# pi3_hat.net
KiCad netlist of a schematic drawn in EAGLE
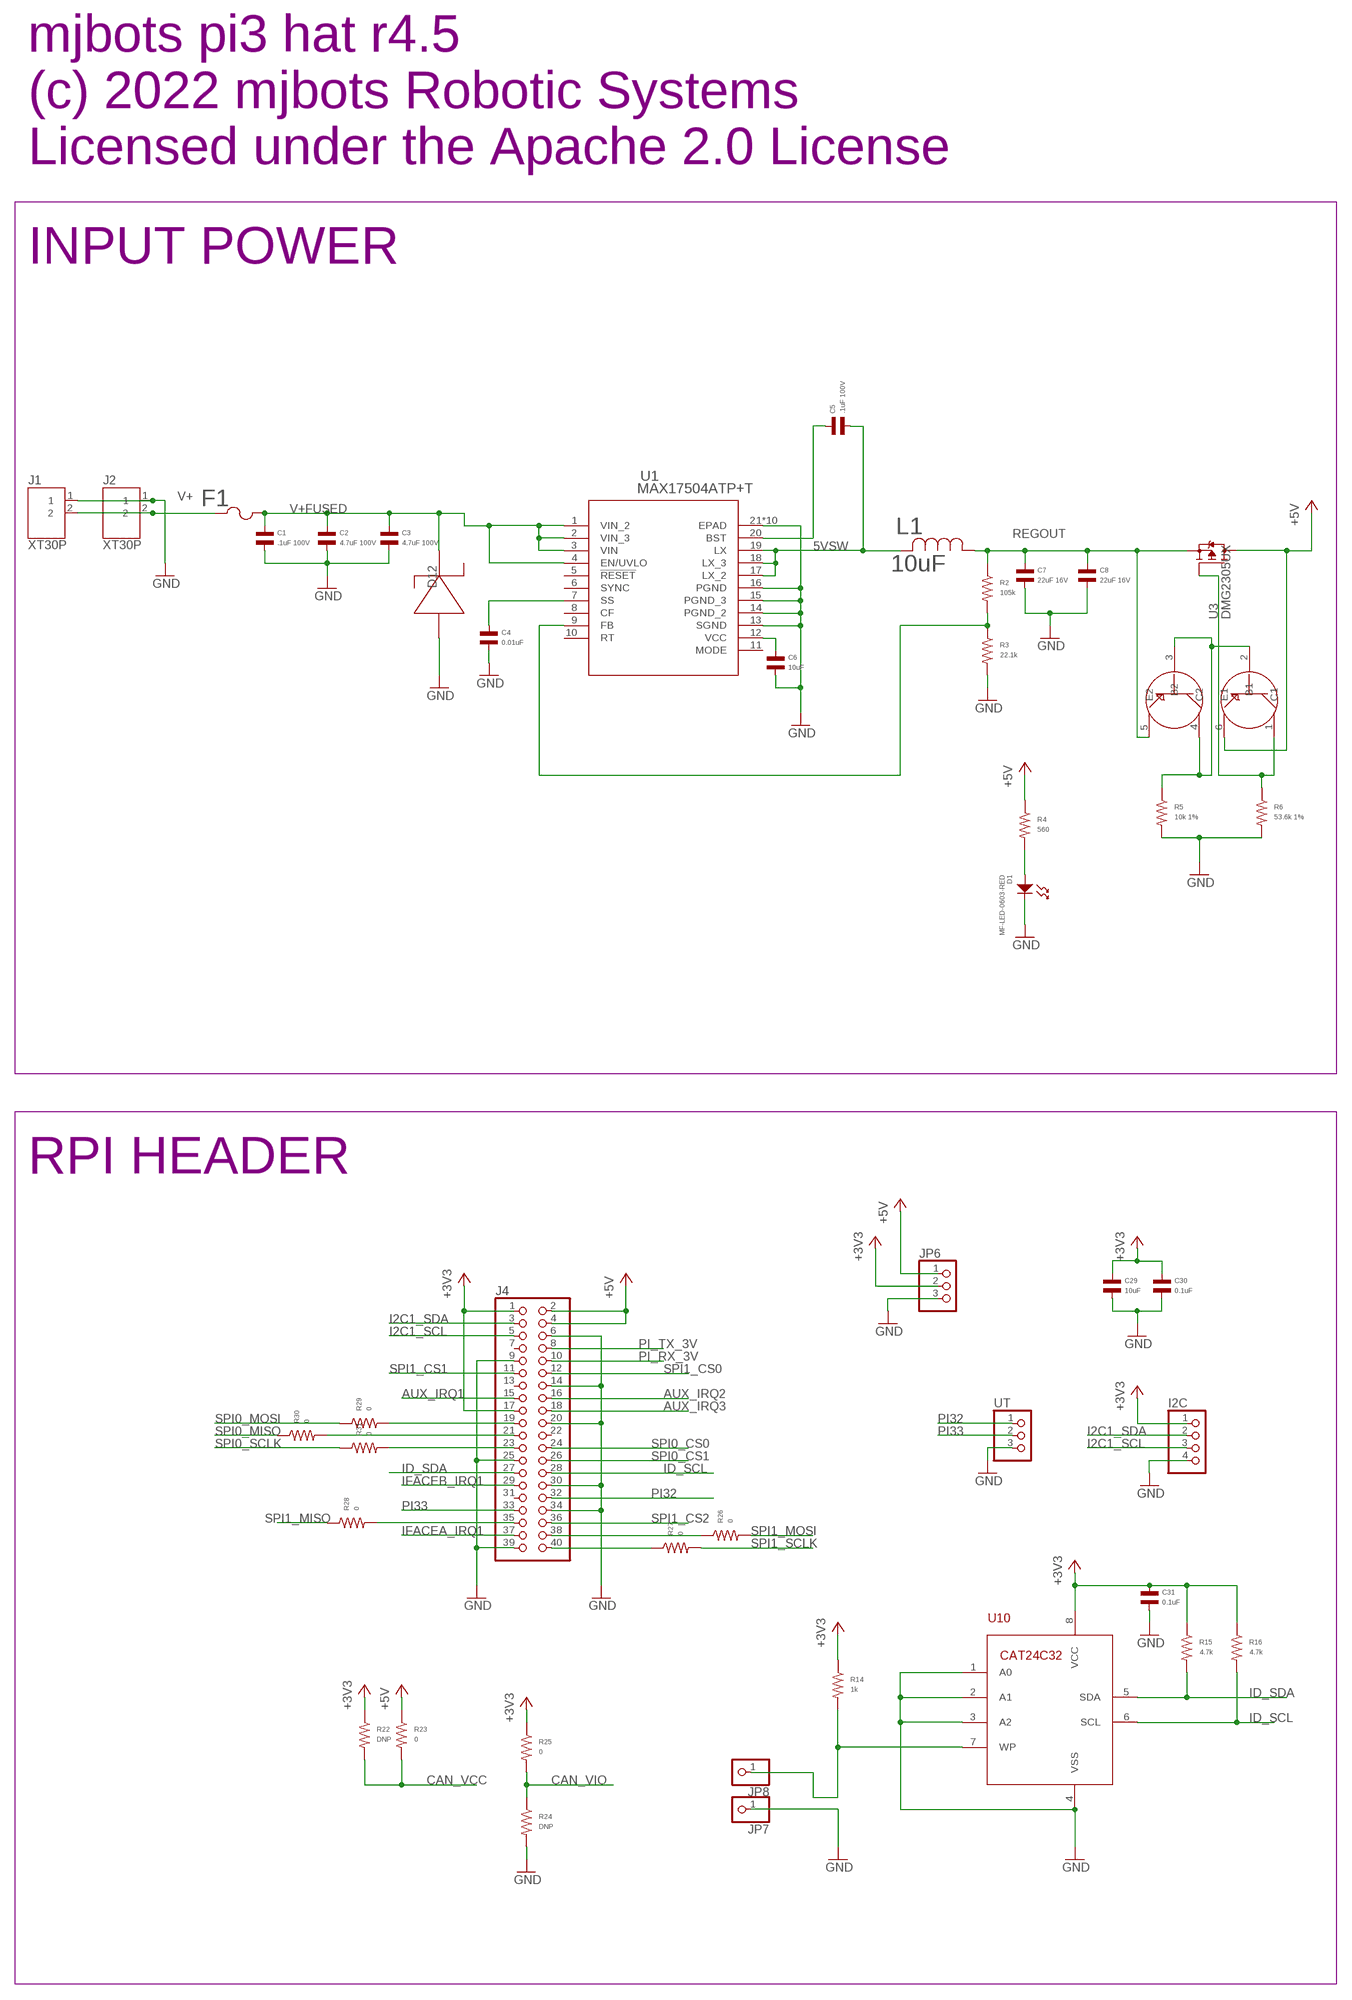
[diagram p0: schematic, sheet 1, part 1 of 3]
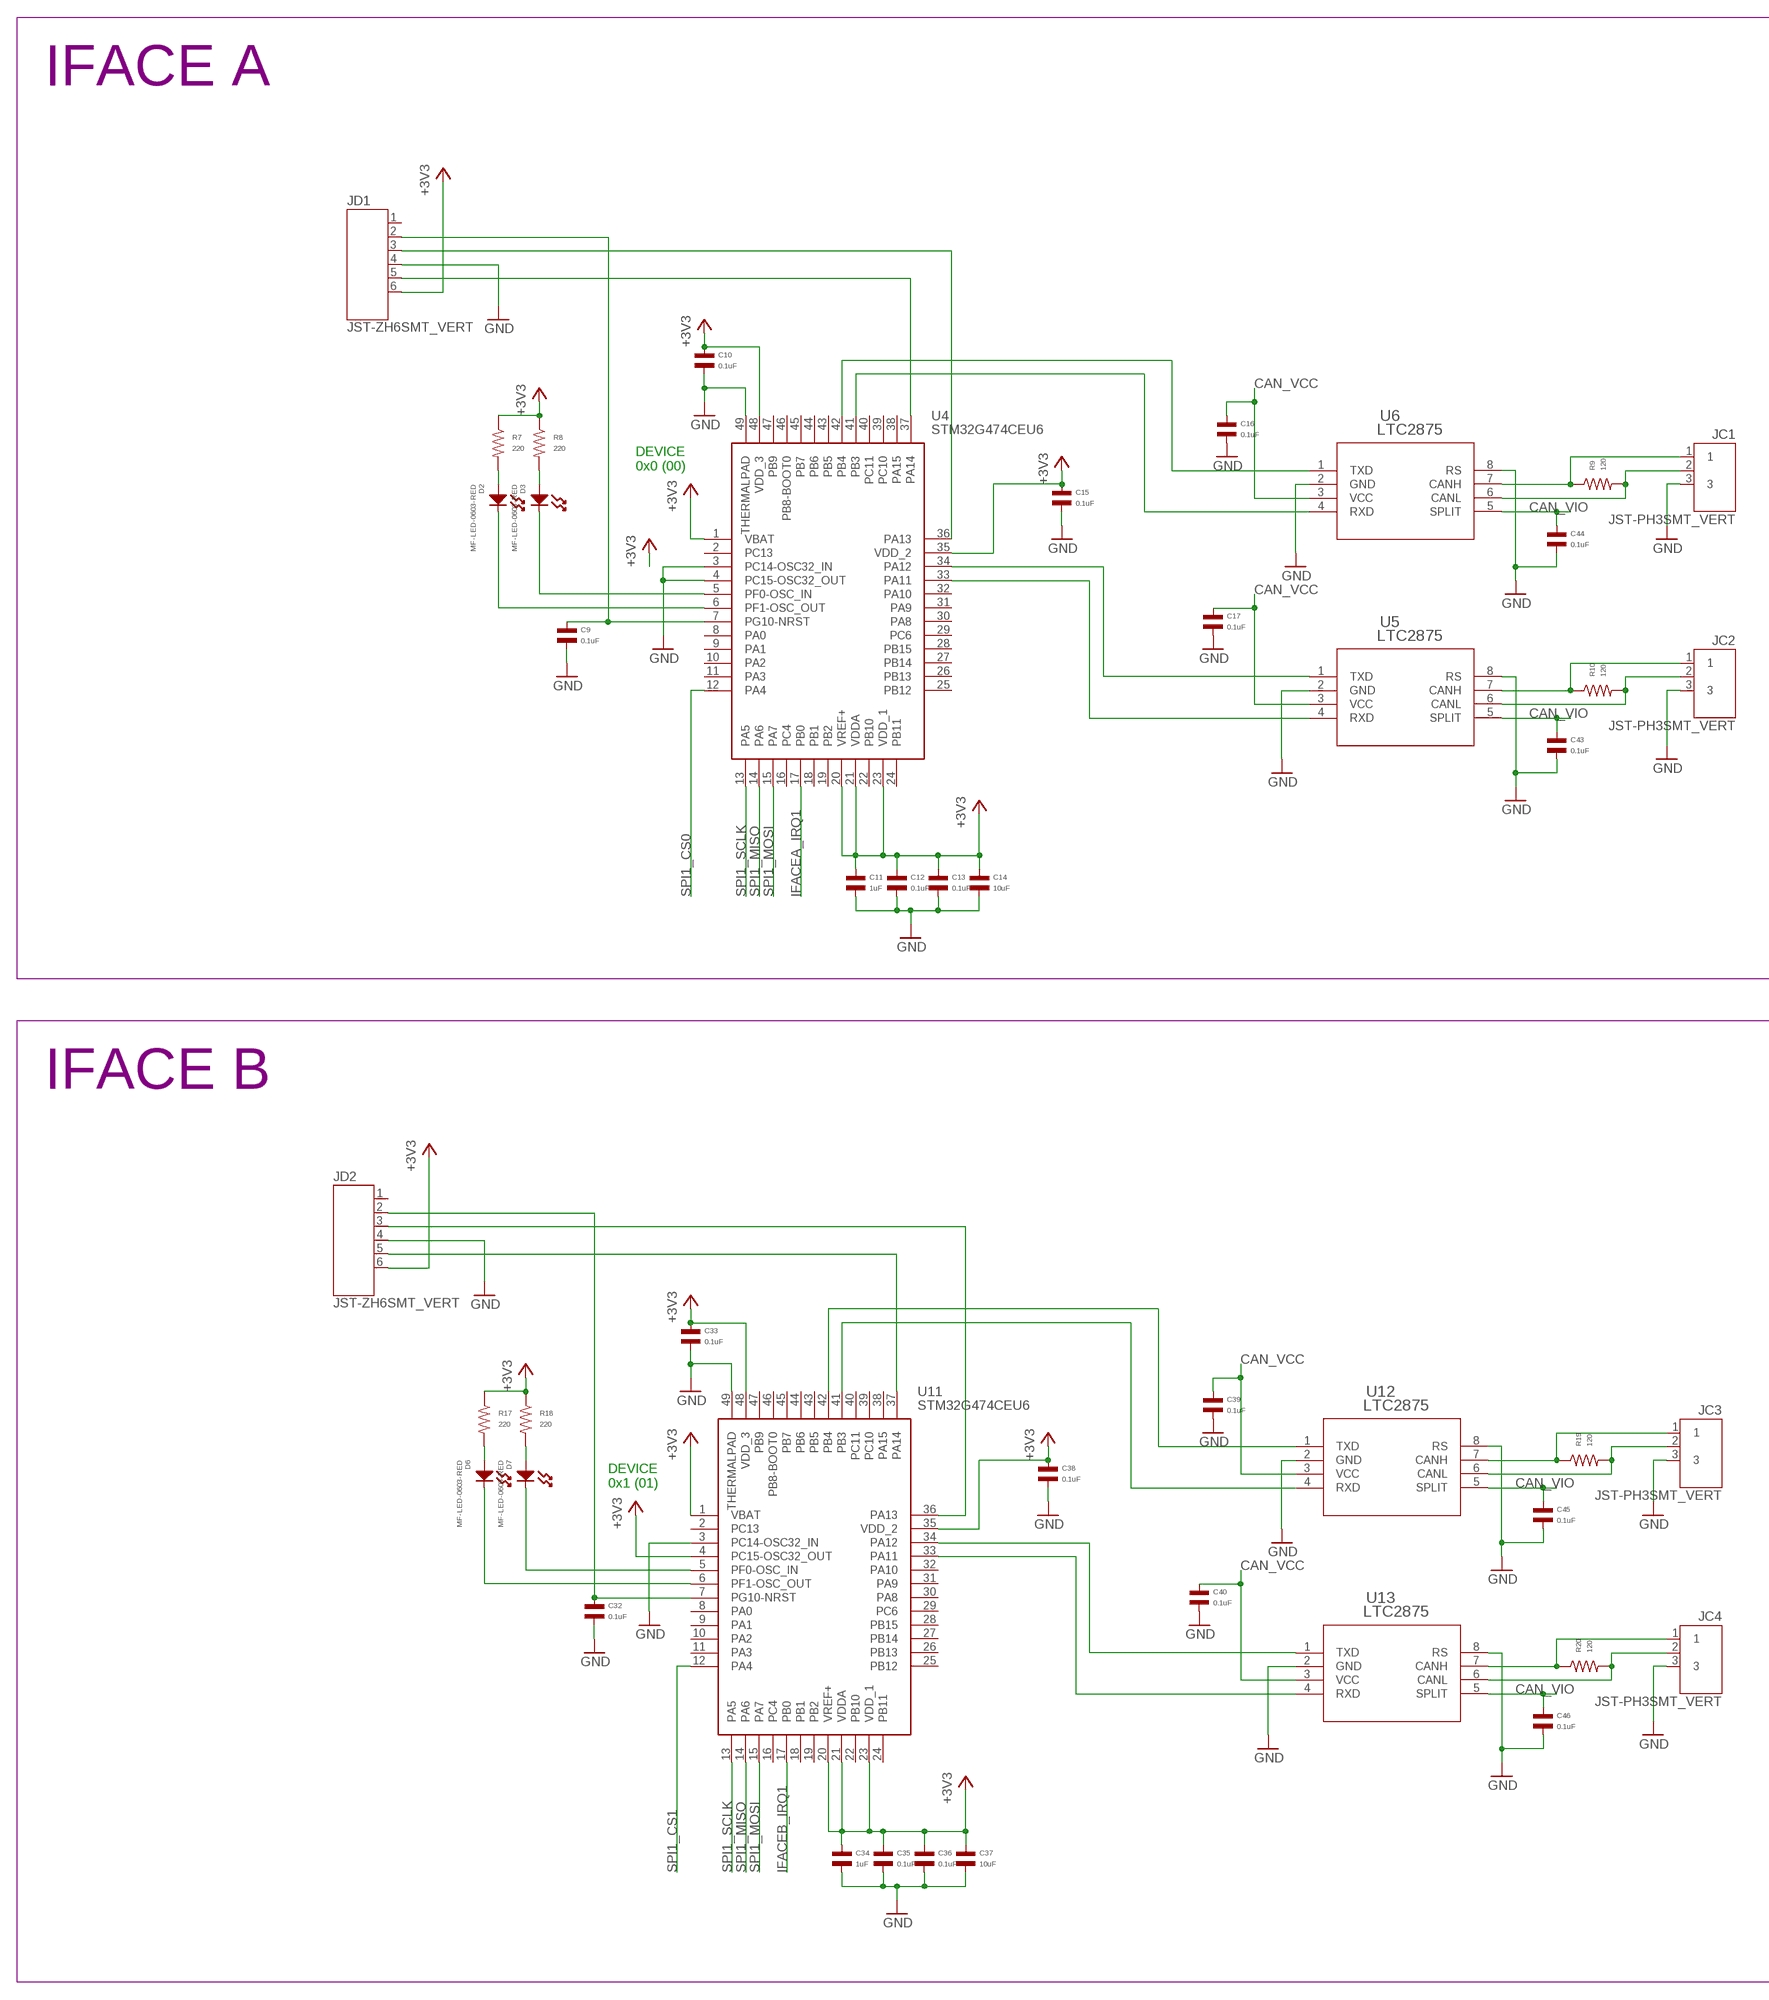
[diagram p1: schematic, sheet 1, part 2 of 3]
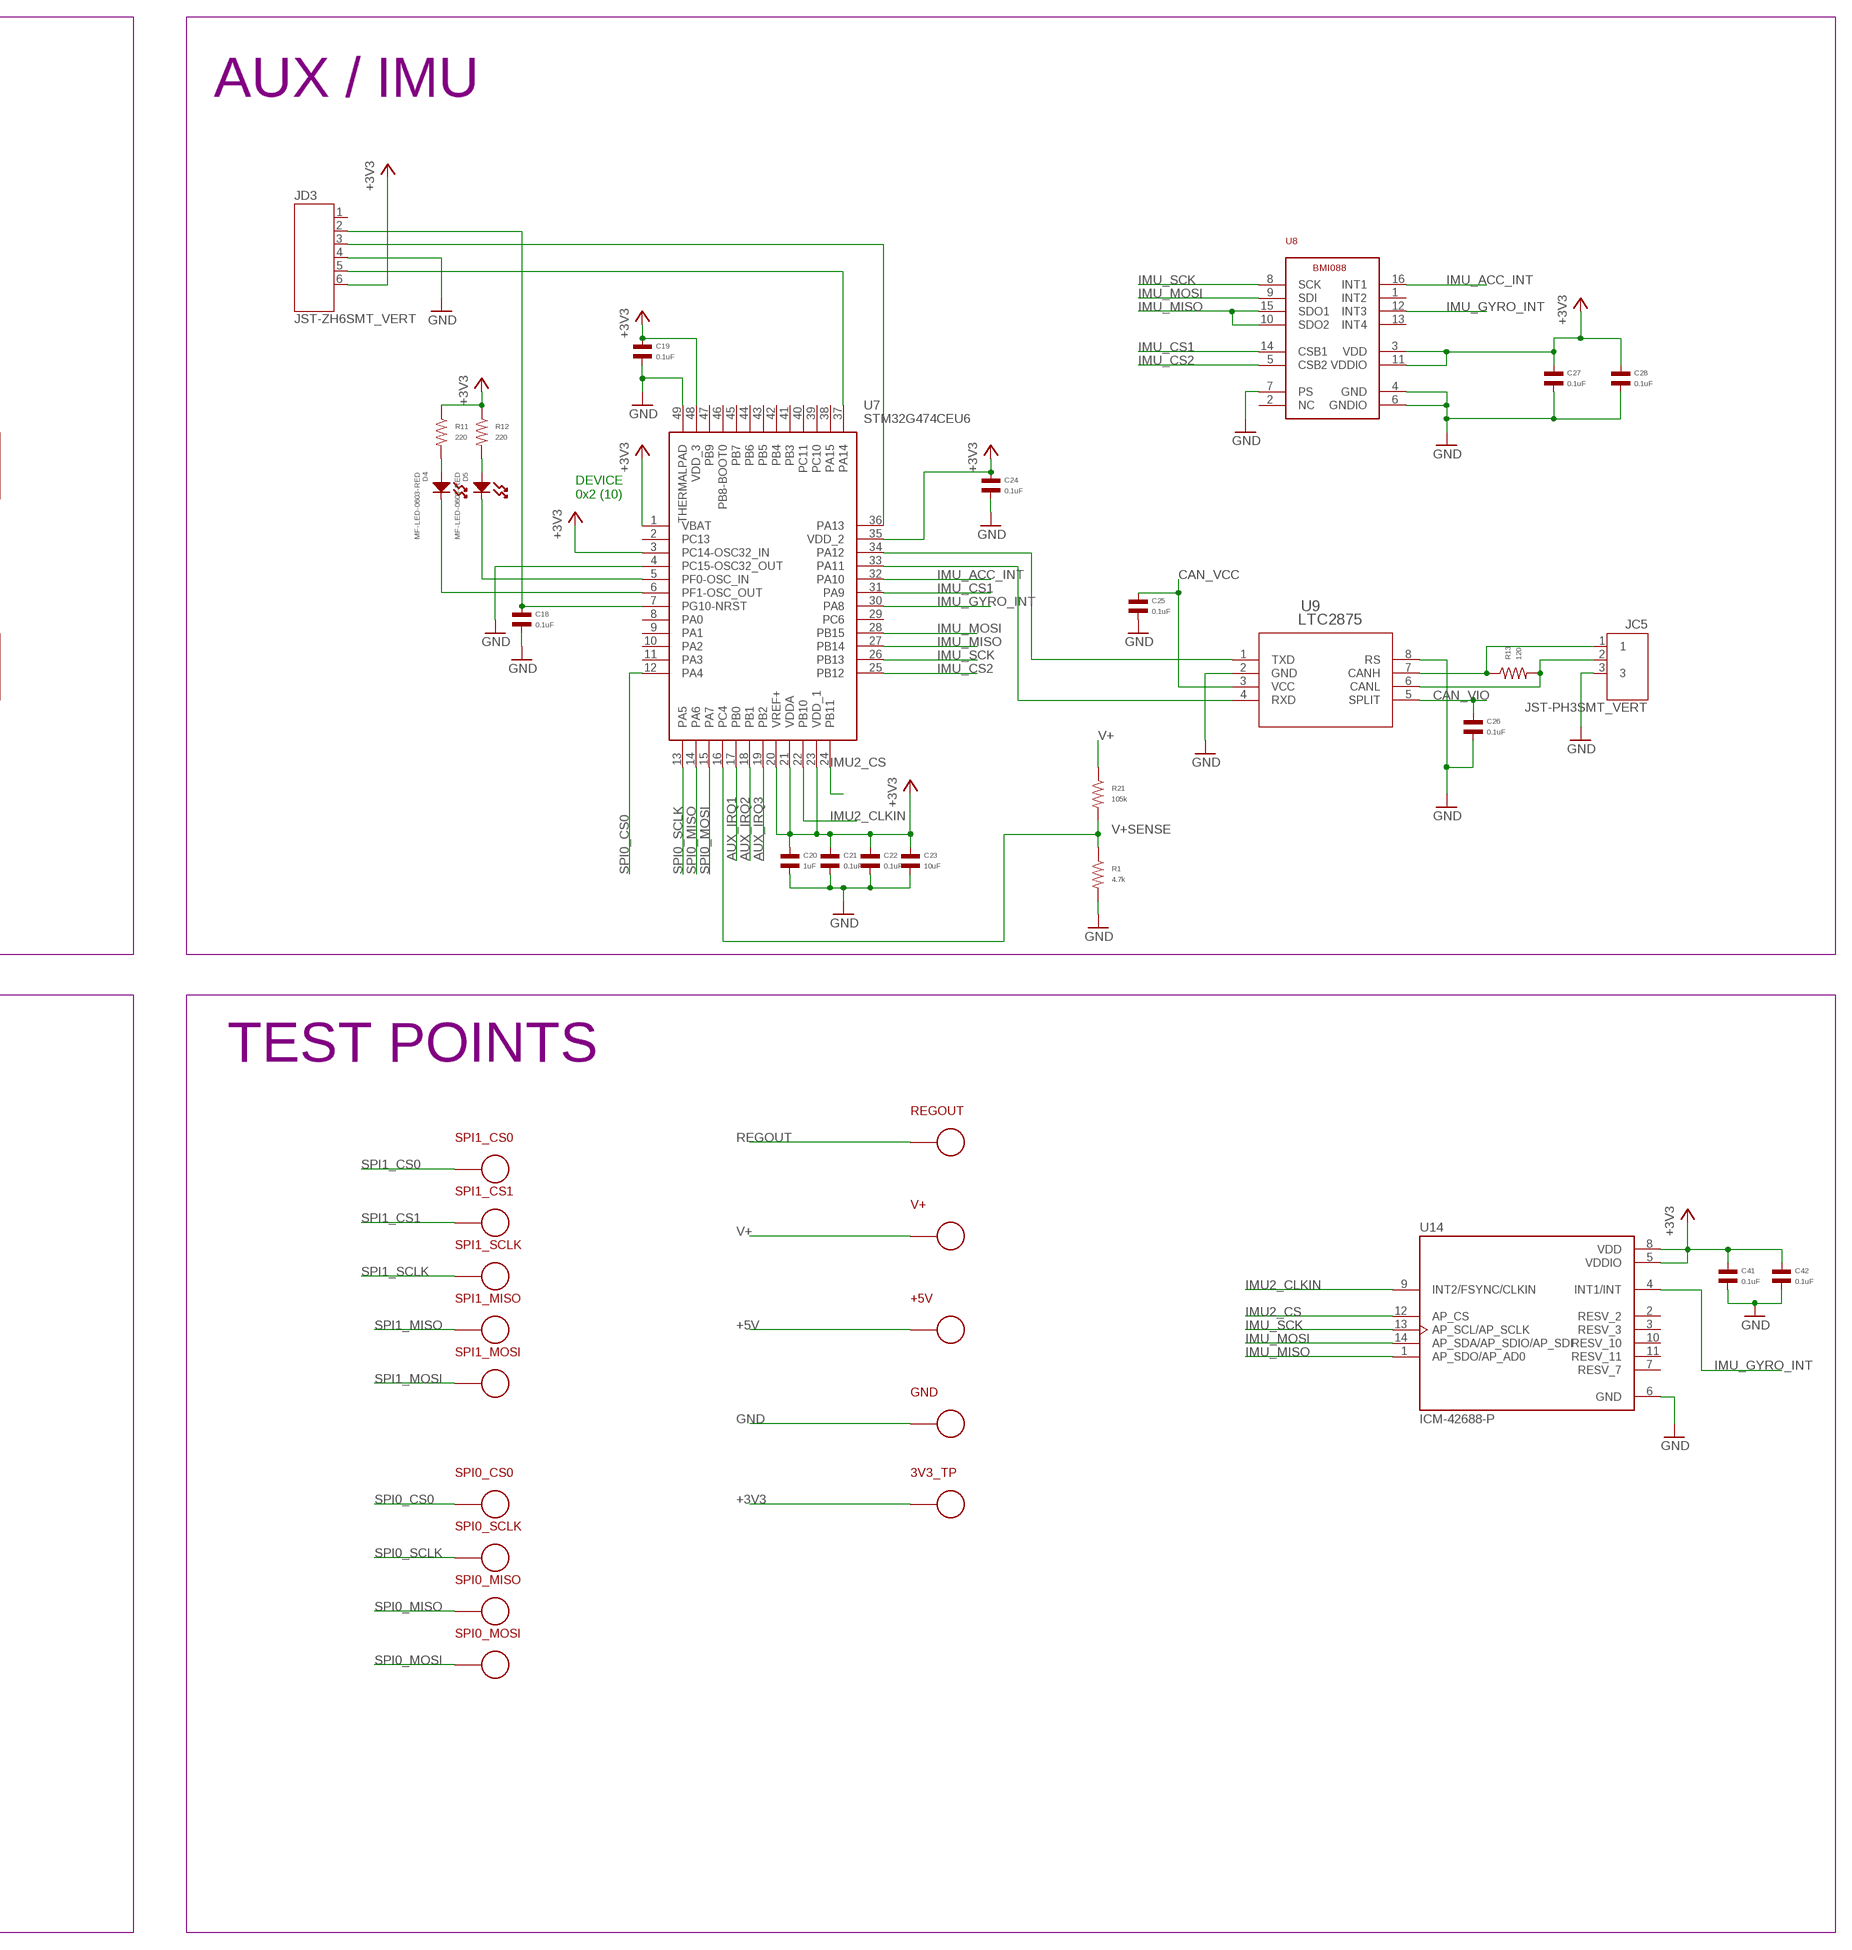
[diagram p2: schematic, sheet 1, part 3 of 3]

(export (version "E")
  (design (tool "Eeschema 10.0.6"))
  (components
    (comp (ref "+5V")
      (value "PAD24AWG_PAD")
      (footprint "eagle-import:24AWG_PAD")
      (libsource (lib "eagle-import") (part "PAD24AWG_PAD"))
    )
    (comp (ref "3V3_TP")
      (value "PAD24AWG_PAD")
      (footprint "eagle-import:24AWG_PAD")
      (libsource (lib "eagle-import") (part "PAD24AWG_PAD"))
    )
    (comp (ref "C1")
      (value ".1uF 100V")
      (footprint "eagle-import:C0805")
      (fields
        (field (name "HOUSEPART") "0")
        (field (name "MF") "KYOCERA")
        (field (name "MPN") "08051C104KAZ2A")
      )
      (libsource (lib "eagle-import") (part "CAPACITOR_NP_0805"))
    )
    (comp (ref "C2")
      (value "4.7uF 100V")
      (footprint "eagle-import:C1206")
      (fields (field (name "MF") "MURATA") (field (name "MPN") "GRJ31CC72A475KE01K"))
      (libsource (lib "eagle-import") (part "CAPACITOR_NP_1206"))
    )
    (comp (ref "C3")
      (value "4.7uF 100V")
      (footprint "eagle-import:C1206")
      (fields (field (name "MF") "MURATA") (field (name "MPN") "GRJ31CC72A475KE01K"))
      (libsource (lib "eagle-import") (part "CAPACITOR_NP_1206"))
    )
    (comp (ref "C4")
      (value "0.01uF")
      (footprint "eagle-import:C0603")
      (fields (field (name "MPN") "MF-CAP-0603-0.01uF"))
      (libsource (lib "eagle-import") (part "CAPACITOR_NP_0603"))
    )
    (comp (ref "C5")
      (value ".1uF 100V")
      (footprint "eagle-import:C0805")
      (fields
        (field (name "HOUSEPART") "0")
        (field (name "MF") "KYOCERA")
        (field (name "MPN") "08051C104KAZ2A")
      )
      (libsource (lib "eagle-import") (part "CAPACITOR_NP_0805"))
    )
    (comp (ref "C6")
      (value "10uF")
      (footprint "eagle-import:C1206")
      (fields (field (name "HOUSEPART") "YES") (field (name "MPN") "MF-CAP-1206-10uF"))
      (libsource (lib "eagle-import") (part "CAPACITOR_NP_1206"))
    )
    (comp (ref "C7")
      (value "22uF 16V")
      (footprint "eagle-import:C1210")
      (fields (field (name "MF") "SAMSUNG") (field (name "MPN") "CL32A226KOJNNNE"))
      (libsource (lib "eagle-import") (part "CAPACITOR_NP_1210"))
    )
    (comp (ref "C8")
      (value "22uF 16V")
      (footprint "eagle-import:C1210")
      (fields (field (name "MF") "SAMSUNG") (field (name "MPN") "CL32A226KOJNNNE"))
      (libsource (lib "eagle-import") (part "CAPACITOR_NP_1210"))
    )
    (comp (ref "C9")
      (value "0.1uF")
      (footprint "eagle-import:C0402")
      (fields (field (name "HOUSEPART") "YES") (field (name "MPN") "MF-CAP-0402-0.1uF"))
      (libsource (lib "eagle-import") (part "CAPACITOR_NP_0402"))
    )
    (comp (ref "C10")
      (value "0.1uF")
      (footprint "eagle-import:C0402")
      (fields (field (name "HOUSEPART") "YES") (field (name "MPN") "MF-CAP-0402-0.1uF"))
      (libsource (lib "eagle-import") (part "CAPACITOR_NP_0402"))
    )
    (comp (ref "C11")
      (value "1uF")
      (footprint "eagle-import:C0402")
      (fields (field (name "HOUSEPART") "YES") (field (name "MPN") "MF-CAP-0402-1uF"))
      (libsource (lib "eagle-import") (part "CAPACITOR_NP_0402"))
    )
    (comp (ref "C12")
      (value "0.1uF")
      (footprint "eagle-import:C0402")
      (fields (field (name "HOUSEPART") "YES") (field (name "MPN") "MF-CAP-0402-0.1uF"))
      (libsource (lib "eagle-import") (part "CAPACITOR_NP_0402"))
    )
    (comp (ref "C13")
      (value "0.1uF")
      (footprint "eagle-import:C0402")
      (fields (field (name "HOUSEPART") "YES") (field (name "MPN") "MF-CAP-0402-0.1uF"))
      (libsource (lib "eagle-import") (part "CAPACITOR_NP_0402"))
    )
    (comp (ref "C14")
      (value "10uF")
      (footprint "eagle-import:C1206")
      (fields (field (name "HOUSEPART") "YES") (field (name "MPN") "MF-CAP-1206-10uF"))
      (libsource (lib "eagle-import") (part "CAPACITOR_NP_1206"))
    )
    (comp (ref "C15")
      (value "0.1uF")
      (footprint "eagle-import:C0402")
      (fields (field (name "HOUSEPART") "YES") (field (name "MPN") "MF-CAP-0402-0.1uF"))
      (libsource (lib "eagle-import") (part "CAPACITOR_NP_0402"))
    )
    (comp (ref "C16")
      (value "0.1uF")
      (footprint "eagle-import:C0402")
      (fields (field (name "HOUSEPART") "YES") (field (name "MPN") "MF-CAP-0402-0.1uF"))
      (libsource (lib "eagle-import") (part "CAPACITOR_NP_0402"))
    )
    (comp (ref "C17")
      (value "0.1uF")
      (footprint "eagle-import:C0402")
      (fields (field (name "HOUSEPART") "YES") (field (name "MPN") "MF-CAP-0402-0.1uF"))
      (libsource (lib "eagle-import") (part "CAPACITOR_NP_0402"))
    )
    (comp (ref "C18")
      (value "0.1uF")
      (footprint "eagle-import:C0402")
      (fields (field (name "HOUSEPART") "YES") (field (name "MPN") "MF-CAP-0402-0.1uF"))
      (libsource (lib "eagle-import") (part "CAPACITOR_NP_0402"))
    )
    (comp (ref "C19")
      (value "0.1uF")
      (footprint "eagle-import:C0402")
      (fields (field (name "HOUSEPART") "YES") (field (name "MPN") "MF-CAP-0402-0.1uF"))
      (libsource (lib "eagle-import") (part "CAPACITOR_NP_0402"))
    )
    (comp (ref "C20")
      (value "1uF")
      (footprint "eagle-import:C0402")
      (fields (field (name "HOUSEPART") "YES") (field (name "MPN") "MF-CAP-0402-1uF"))
      (libsource (lib "eagle-import") (part "CAPACITOR_NP_0402"))
    )
    (comp (ref "C21")
      (value "0.1uF")
      (footprint "eagle-import:C0402")
      (fields (field (name "HOUSEPART") "YES") (field (name "MPN") "MF-CAP-0402-0.1uF"))
      (libsource (lib "eagle-import") (part "CAPACITOR_NP_0402"))
    )
    (comp (ref "C22")
      (value "0.1uF")
      (footprint "eagle-import:C0402")
      (fields (field (name "HOUSEPART") "YES") (field (name "MPN") "MF-CAP-0402-0.1uF"))
      (libsource (lib "eagle-import") (part "CAPACITOR_NP_0402"))
    )
    (comp (ref "C23")
      (value "10uF")
      (footprint "eagle-import:C1206")
      (fields (field (name "HOUSEPART") "YES") (field (name "MPN") "MF-CAP-1206-10uF"))
      (libsource (lib "eagle-import") (part "CAPACITOR_NP_1206"))
    )
    (comp (ref "C24")
      (value "0.1uF")
      (footprint "eagle-import:C0402")
      (fields (field (name "HOUSEPART") "YES") (field (name "MPN") "MF-CAP-0402-0.1uF"))
      (libsource (lib "eagle-import") (part "CAPACITOR_NP_0402"))
    )
    (comp (ref "C25")
      (value "0.1uF")
      (footprint "eagle-import:C0402")
      (fields (field (name "HOUSEPART") "YES") (field (name "MPN") "MF-CAP-0402-0.1uF"))
      (libsource (lib "eagle-import") (part "CAPACITOR_NP_0402"))
    )
    (comp (ref "C26")
      (value "0.1uF")
      (footprint "eagle-import:C0402")
      (fields (field (name "HOUSEPART") "YES") (field (name "MPN") "MF-CAP-0402-0.1uF"))
      (libsource (lib "eagle-import") (part "CAPACITOR_NP_0402"))
    )
    (comp (ref "C27")
      (value "0.1uF")
      (footprint "eagle-import:C0402")
      (fields (field (name "HOUSEPART") "YES") (field (name "MPN") "MF-CAP-0402-0.1uF"))
      (libsource (lib "eagle-import") (part "CAPACITOR_NP_0402"))
    )
    (comp (ref "C28")
      (value "0.1uF")
      (footprint "eagle-import:C0402")
      (fields (field (name "HOUSEPART") "YES") (field (name "MPN") "MF-CAP-0402-0.1uF"))
      (libsource (lib "eagle-import") (part "CAPACITOR_NP_0402"))
    )
    (comp (ref "C29")
      (value "10uF")
      (footprint "eagle-import:C1206")
      (fields (field (name "HOUSEPART") "YES") (field (name "MPN") "MF-CAP-1206-10uF"))
      (libsource (lib "eagle-import") (part "CAPACITOR_NP_1206"))
    )
    (comp (ref "C30")
      (value "0.1uF")
      (footprint "eagle-import:C0402")
      (fields (field (name "HOUSEPART") "YES") (field (name "MPN") "MF-CAP-0402-0.1uF"))
      (libsource (lib "eagle-import") (part "CAPACITOR_NP_0402"))
    )
    (comp (ref "C31")
      (value "0.1uF")
      (footprint "eagle-import:C0402")
      (fields (field (name "HOUSEPART") "YES") (field (name "MPN") "MF-CAP-0402-0.1uF"))
      (libsource (lib "eagle-import") (part "CAPACITOR_NP_0402"))
    )
    (comp (ref "C32")
      (value "0.1uF")
      (footprint "eagle-import:C0402")
      (fields (field (name "HOUSEPART") "YES") (field (name "MPN") "MF-CAP-0402-0.1uF"))
      (libsource (lib "eagle-import") (part "CAPACITOR_NP_0402"))
    )
    (comp (ref "C33")
      (value "0.1uF")
      (footprint "eagle-import:C0402")
      (fields (field (name "HOUSEPART") "YES") (field (name "MPN") "MF-CAP-0402-0.1uF"))
      (libsource (lib "eagle-import") (part "CAPACITOR_NP_0402"))
    )
    (comp (ref "C34")
      (value "1uF")
      (footprint "eagle-import:C0402")
      (fields (field (name "HOUSEPART") "YES") (field (name "MPN") "MF-CAP-0402-1uF"))
      (libsource (lib "eagle-import") (part "CAPACITOR_NP_0402"))
    )
    (comp (ref "C35")
      (value "0.1uF")
      (footprint "eagle-import:C0402")
      (fields (field (name "HOUSEPART") "YES") (field (name "MPN") "MF-CAP-0402-0.1uF"))
      (libsource (lib "eagle-import") (part "CAPACITOR_NP_0402"))
    )
    (comp (ref "C36")
      (value "0.1uF")
      (footprint "eagle-import:C0402")
      (fields (field (name "HOUSEPART") "YES") (field (name "MPN") "MF-CAP-0402-0.1uF"))
      (libsource (lib "eagle-import") (part "CAPACITOR_NP_0402"))
    )
    (comp (ref "C37")
      (value "10uF")
      (footprint "eagle-import:C1206")
      (fields (field (name "HOUSEPART") "YES") (field (name "MPN") "MF-CAP-1206-10uF"))
      (libsource (lib "eagle-import") (part "CAPACITOR_NP_1206"))
    )
    (comp (ref "C38")
      (value "0.1uF")
      (footprint "eagle-import:C0402")
      (fields (field (name "HOUSEPART") "YES") (field (name "MPN") "MF-CAP-0402-0.1uF"))
      (libsource (lib "eagle-import") (part "CAPACITOR_NP_0402"))
    )
    (comp (ref "C39")
      (value "0.1uF")
      (footprint "eagle-import:C0402")
      (fields (field (name "HOUSEPART") "YES") (field (name "MPN") "MF-CAP-0402-0.1uF"))
      (libsource (lib "eagle-import") (part "CAPACITOR_NP_0402"))
    )
    (comp (ref "C40")
      (value "0.1uF")
      (footprint "eagle-import:C0402")
      (fields (field (name "HOUSEPART") "YES") (field (name "MPN") "MF-CAP-0402-0.1uF"))
      (libsource (lib "eagle-import") (part "CAPACITOR_NP_0402"))
    )
    (comp (ref "C41")
      (value "0.1uF")
      (footprint "eagle-import:C0402")
      (fields (field (name "HOUSEPART") "YES") (field (name "MPN") "MF-CAP-0402-0.1uF"))
      (libsource (lib "eagle-import") (part "CAPACITOR_NP_0402"))
    )
    (comp (ref "C42")
      (value "0.1uF")
      (footprint "eagle-import:C0402")
      (fields (field (name "HOUSEPART") "YES") (field (name "MPN") "MF-CAP-0402-0.1uF"))
      (libsource (lib "eagle-import") (part "CAPACITOR_NP_0402"))
    )
    (comp (ref "C43")
      (value "0.1uF")
      (footprint "eagle-import:C0402")
      (fields (field (name "HOUSEPART") "YES") (field (name "MPN") "MF-CAP-0402-0.1uF"))
      (libsource (lib "eagle-import") (part "CAPACITOR_NP_0402"))
    )
    (comp (ref "C44")
      (value "0.1uF")
      (footprint "eagle-import:C0402")
      (fields (field (name "HOUSEPART") "YES") (field (name "MPN") "MF-CAP-0402-0.1uF"))
      (libsource (lib "eagle-import") (part "CAPACITOR_NP_0402"))
    )
    (comp (ref "C45")
      (value "0.1uF")
      (footprint "eagle-import:C0402")
      (fields (field (name "HOUSEPART") "YES") (field (name "MPN") "MF-CAP-0402-0.1uF"))
      (libsource (lib "eagle-import") (part "CAPACITOR_NP_0402"))
    )
    (comp (ref "C46")
      (value "0.1uF")
      (footprint "eagle-import:C0402")
      (fields (field (name "HOUSEPART") "YES") (field (name "MPN") "MF-CAP-0402-0.1uF"))
      (libsource (lib "eagle-import") (part "CAPACITOR_NP_0402"))
    )
    (comp (ref "D1")
      (value "MF-LED-0603-RED")
      (footprint "eagle-import:LED0603")
      (fields (field (name "HOUSEPART") "YES"))
      (libsource (lib "eagle-import") (part "LED_SINGLE-0603-RED"))
    )
    (comp (ref "D2")
      (value "MF-LED-0603-RED")
      (footprint "eagle-import:LED0603")
      (fields (field (name "HOUSEPART") "YES"))
      (libsource (lib "eagle-import") (part "LED_SINGLE-0603-RED"))
    )
    (comp (ref "D3")
      (value "MF-LED-0603-RED")
      (footprint "eagle-import:LED0603")
      (fields (field (name "HOUSEPART") "YES") (field (name "MPN") "MF-LED-0603-GREEN"))
      (libsource (lib "eagle-import") (part "LED_SINGLE-0603-RED"))
    )
    (comp (ref "D4")
      (value "MF-LED-0603-RED")
      (footprint "eagle-import:LED0603")
      (fields (field (name "HOUSEPART") "YES"))
      (libsource (lib "eagle-import") (part "LED_SINGLE-0603-RED"))
    )
    (comp (ref "D5")
      (value "MF-LED-0603-RED")
      (footprint "eagle-import:LED0603")
      (fields (field (name "HOUSEPART") "YES") (field (name "MPN") "MF-LED-0603-GREEN"))
      (libsource (lib "eagle-import") (part "LED_SINGLE-0603-RED"))
    )
    (comp (ref "D6")
      (value "MF-LED-0603-RED")
      (footprint "eagle-import:LED0603")
      (fields (field (name "HOUSEPART") "YES"))
      (libsource (lib "eagle-import") (part "LED_SINGLE-0603-RED"))
    )
    (comp (ref "D7")
      (value "MF-LED-0603-RED")
      (footprint "eagle-import:LED0603")
      (fields (field (name "HOUSEPART") "YES") (field (name "MPN") "MF-LED-0603-GREEN"))
      (libsource (lib "eagle-import") (part "LED_SINGLE-0603-RED"))
    )
    (comp (ref "D12")
      (value "SMF")
      (footprint "eagle-import:SMF")
      (fields (field (name "MF") "LITTLEFUSE") (field (name "MPN") "SMF51A"))
      (libsource (lib "eagle-import") (part "SMF"))
    )
    (comp (ref "F1")
      (value "MFU0603FF04000P100")
      (footprint "eagle-import:FUS_VISHAY_MFU0603")
      (fields
        (field (name "MF") "BEL FUSE")
        (field (name "MPN") "0686F4000-01")
        (field (name "VENDOR") "BEL FUSE")
      )
      (libsource (lib "eagle-import") (part "MFU0603FF04000P100"))
    )
    (comp (ref "GND")
      (value "PAD24AWG_PAD")
      (footprint "eagle-import:24AWG_PAD")
      (libsource (lib "eagle-import") (part "PAD24AWG_PAD"))
    )
    (comp (ref "I2C")
      (value "PINHD-1X4")
      (footprint "eagle-import:1X04")
      (fields (field (name "MF") "MacroFab") (field (name "MPN") "MF-CON-2.54mm-01x04"))
      (libsource (lib "eagle-import") (part "PINHD-1X4"))
    )
    (comp (ref "J1")
      (value "XT30P")
      (footprint "eagle-import:XT30P")
      (fields (field (name "MF") "AMASS") (field (name "MPN") "XT30UPB-M"))
      (libsource (lib "eagle-import") (part "XT30P"))
    )
    (comp (ref "J2")
      (value "XT30P")
      (footprint "eagle-import:XT30P")
      (fields (field (name "MF") "AMASS") (field (name "MPN") "XT30UPB-M"))
      (libsource (lib "eagle-import") (part "XT30P"))
    )
    (comp (ref "J4")
      (value "PI3_HEADER2X20-FLIP")
      (footprint "eagle-import:2X20FLIP")
      (fields (field (name "MF") "SULLINS") (field (name "MPN") "PPPC202LFBN-RC"))
      (libsource (lib "eagle-import") (part "PI3_HEADER2X20-FLIP"))
    )
    (comp (ref "JC1")
      (value "JST-PH3SMT_VERT")
      (footprint "eagle-import:JST_B3B_PH-SM4-TB(LF)(SN)")
      (fields (field (name "MF") "JST") (field (name "MPN") "B3B-PH-SM4-TB(LF)(SN)"))
      (libsource (lib "eagle-import") (part "JST-PH3SMT_VERT"))
    )
    (comp (ref "JC2")
      (value "JST-PH3SMT_VERT")
      (footprint "eagle-import:JST_B3B_PH-SM4-TB(LF)(SN)")
      (fields (field (name "MF") "JST") (field (name "MPN") "B3B-PH-SM4-TB(LF)(SN)"))
      (libsource (lib "eagle-import") (part "JST-PH3SMT_VERT"))
    )
    (comp (ref "JC3")
      (value "JST-PH3SMT_VERT")
      (footprint "eagle-import:JST_B3B_PH-SM4-TB(LF)(SN)")
      (fields (field (name "MF") "JST") (field (name "MPN") "B3B-PH-SM4-TB(LF)(SN)"))
      (libsource (lib "eagle-import") (part "JST-PH3SMT_VERT"))
    )
    (comp (ref "JC4")
      (value "JST-PH3SMT_VERT")
      (footprint "eagle-import:JST_B3B_PH-SM4-TB(LF)(SN)")
      (fields (field (name "MF") "JST") (field (name "MPN") "B3B-PH-SM4-TB(LF)(SN)"))
      (libsource (lib "eagle-import") (part "JST-PH3SMT_VERT"))
    )
    (comp (ref "JC5")
      (value "JST-PH3SMT_VERT")
      (footprint "eagle-import:JST_B3B_PH-SM4-TB(LF)(SN)")
      (fields (field (name "MF") "JST") (field (name "MPN") "B3B-PH-SM4-TB(LF)(SN)"))
      (libsource (lib "eagle-import") (part "JST-PH3SMT_VERT"))
    )
    (comp (ref "JD1")
      (value "JST-ZH6SMT_VERT")
      (footprint "eagle-import:JST_B6B-ZR-SM4-TF(LF)(SN)")
      (fields (field (name "MF") "JST") (field (name "MPN") "B6B-ZR-SM4-TF(LF)(SN)"))
      (libsource (lib "eagle-import") (part "JST-ZH6SMT_VERT"))
    )
    (comp (ref "JD2")
      (value "JST-ZH6SMT_VERT")
      (footprint "eagle-import:JST_B6B-ZR-SM4-TF(LF)(SN)")
      (fields (field (name "MF") "JST") (field (name "MPN") "B6B-ZR-SM4-TF(LF)(SN)"))
      (libsource (lib "eagle-import") (part "JST-ZH6SMT_VERT"))
    )
    (comp (ref "JD3")
      (value "JST-ZH6SMT_VERT")
      (footprint "eagle-import:JST_B6B-ZR-SM4-TF(LF)(SN)")
      (fields (field (name "MF") "JST") (field (name "MPN") "B6B-ZR-SM4-TF(LF)(SN)"))
      (libsource (lib "eagle-import") (part "JST-ZH6SMT_VERT"))
    )
    (comp (ref "JP6")
      (value "PINHD-1X3")
      (footprint "eagle-import:1X03")
      (fields (field (name "MF") "MacroFab") (field (name "MPN") "MF-CON-2.54mm-01x03"))
      (libsource (lib "eagle-import") (part "PINHD-1X3"))
    )
    (comp (ref "JP7")
      (value "PINHD-1X1")
      (footprint "eagle-import:1X01")
      (libsource (lib "eagle-import") (part "PINHD-1X1"))
    )
    (comp (ref "JP8")
      (value "PINHD-1X1")
      (footprint "eagle-import:1X01")
      (libsource (lib "eagle-import") (part "PINHD-1X1"))
    )
    (comp (ref "L1")
      (value "10uF")
      (footprint "eagle-import:IND_YUDEN_NS10165_YDN")
      (fields (field (name "MANUFACTURER_PART_NUMBER") "NS10165T100MNA"))
      (libsource (lib "eagle-import") (part "NS10165T100MNA"))
    )
    (comp (ref "R1")
      (value "4.7k")
      (footprint "eagle-import:R0402")
      (fields (field (name "HOUSEPART") "YES") (field (name "MPN") "MF-RES-0402-4.7K"))
      (libsource (lib "eagle-import") (part "RESISTOR_0402"))
    )
    (comp (ref "R2")
      (value "105k")
      (footprint "eagle-import:R0402")
      (fields (field (name "MF") "YAGEO") (field (name "MPN") "RC0402FR-07105KL"))
      (libsource (lib "eagle-import") (part "RESISTOR_0402"))
    )
    (comp (ref "R3")
      (value "22.1k")
      (footprint "eagle-import:R0402")
      (fields (field (name "MF") "YAGEO") (field (name "MPN") "RC0402FR-0722K1L"))
      (libsource (lib "eagle-import") (part "RESISTOR_0402"))
    )
    (comp (ref "R4")
      (value "560")
      (footprint "eagle-import:R0402")
      (fields (field (name "HOUSEPART") "YES") (field (name "MPN") "MF-RES-0402-560"))
      (libsource (lib "eagle-import") (part "RESISTOR_0402"))
    )
    (comp (ref "R5")
      (value "10k 1%")
      (footprint "eagle-import:R0603")
      (fields (field (name "MF") "YAGEO") (field (name "MPN") "RC0603FR-0710KL"))
      (libsource (lib "eagle-import") (part "RESISTOR_0603"))
    )
    (comp (ref "R6")
      (value "53.6k 1%")
      (footprint "eagle-import:R0603")
      (fields (field (name "MF") "YAGEO") (field (name "MPN") "RC0603FR-0753K6L"))
      (libsource (lib "eagle-import") (part "RESISTOR_0603"))
    )
    (comp (ref "R7")
      (value "220")
      (footprint "eagle-import:R0402")
      (fields (field (name "HOUSEPART") "YES") (field (name "MPN") "MF-RES-0402-220"))
      (libsource (lib "eagle-import") (part "RESISTOR_0402"))
    )
    (comp (ref "R8")
      (value "220")
      (footprint "eagle-import:R0402")
      (fields (field (name "HOUSEPART") "YES") (field (name "MPN") "MF-RES-0402-220"))
      (libsource (lib "eagle-import") (part "RESISTOR_0402"))
    )
    (comp (ref "R9")
      (value "120")
      (footprint "eagle-import:R0402")
      (fields (field (name "HOUSEPART") "0") (field (name "MPN") "RC0402FR-07120RL"))
      (libsource (lib "eagle-import") (part "RESISTOR_0402"))
    )
    (comp (ref "R10")
      (value "120")
      (footprint "eagle-import:R0402")
      (fields (field (name "HOUSEPART") "0") (field (name "MPN") "RC0402FR-07120RL"))
      (libsource (lib "eagle-import") (part "RESISTOR_0402"))
    )
    (comp (ref "R11")
      (value "220")
      (footprint "eagle-import:R0402")
      (fields (field (name "HOUSEPART") "YES") (field (name "MPN") "MF-RES-0402-220"))
      (libsource (lib "eagle-import") (part "RESISTOR_0402"))
    )
    (comp (ref "R12")
      (value "220")
      (footprint "eagle-import:R0402")
      (fields (field (name "HOUSEPART") "YES") (field (name "MPN") "MF-RES-0402-220"))
      (libsource (lib "eagle-import") (part "RESISTOR_0402"))
    )
    (comp (ref "R13")
      (value "120")
      (footprint "eagle-import:R0402")
      (fields (field (name "HOUSEPART") "0") (field (name "MPN") "RC0402FR-07120RL"))
      (libsource (lib "eagle-import") (part "RESISTOR_0402"))
    )
    (comp (ref "R14")
      (value "1k")
      (footprint "eagle-import:R0402")
      (fields (field (name "HOUSEPART") "YES") (field (name "MPN") "MF-RES-0402-1K"))
      (libsource (lib "eagle-import") (part "RESISTOR_0402"))
    )
    (comp (ref "R15")
      (value "4.7k")
      (footprint "eagle-import:R0402")
      (fields (field (name "HOUSEPART") "YES") (field (name "MPN") "MF-RES-0402-4.7K"))
      (libsource (lib "eagle-import") (part "RESISTOR_0402"))
    )
    (comp (ref "R16")
      (value "4.7k")
      (footprint "eagle-import:R0402")
      (fields (field (name "HOUSEPART") "YES") (field (name "MPN") "MF-RES-0402-4.7K"))
      (libsource (lib "eagle-import") (part "RESISTOR_0402"))
    )
    (comp (ref "R17")
      (value "220")
      (footprint "eagle-import:R0402")
      (fields (field (name "HOUSEPART") "YES") (field (name "MPN") "MF-RES-0402-220"))
      (libsource (lib "eagle-import") (part "RESISTOR_0402"))
    )
    (comp (ref "R18")
      (value "220")
      (footprint "eagle-import:R0402")
      (fields (field (name "HOUSEPART") "YES") (field (name "MPN") "MF-RES-0402-220"))
      (libsource (lib "eagle-import") (part "RESISTOR_0402"))
    )
    (comp (ref "R19")
      (value "120")
      (footprint "eagle-import:R0402")
      (fields (field (name "HOUSEPART") "0") (field (name "MPN") "RC0402FR-07120RL"))
      (libsource (lib "eagle-import") (part "RESISTOR_0402"))
    )
    (comp (ref "R20")
      (value "120")
      (footprint "eagle-import:R0402")
      (fields (field (name "HOUSEPART") "0") (field (name "MPN") "RC0402FR-07120RL"))
      (libsource (lib "eagle-import") (part "RESISTOR_0402"))
    )
    (comp (ref "R21")
      (value "105k")
      (footprint "eagle-import:R0402")
      (fields (field (name "MF") "YAGEO") (field (name "MPN") "RC0402FR-07105KL"))
      (libsource (lib "eagle-import") (part "RESISTOR_0402"))
    )
    (comp (ref "R22")
      (value "DNP")
      (footprint "eagle-import:R0402")
      (fields
        (field (name "HOUSEPART") "YES")
        (field (name "MPN") "MF-RES-0402-0")
        (field (name "POPULATE") "0")
      )
      (libsource (lib "eagle-import") (part "RESISTOR_0402"))
    )
    (comp (ref "R23")
      (value "0")
      (footprint "eagle-import:R0402")
      (fields (field (name "HOUSEPART") "YES") (field (name "MPN") "MF-RES-0402-0"))
      (libsource (lib "eagle-import") (part "RESISTOR_0402"))
    )
    (comp (ref "R24")
      (value "DNP")
      (footprint "eagle-import:R0402")
      (fields
        (field (name "HOUSEPART") "YES")
        (field (name "MPN") "MF-RES-0402-0")
        (field (name "POPULATE") "0")
      )
      (libsource (lib "eagle-import") (part "RESISTOR_0402"))
    )
    (comp (ref "R25")
      (value "0")
      (footprint "eagle-import:R0402")
      (fields (field (name "HOUSEPART") "YES") (field (name "MPN") "MF-RES-0402-0"))
      (libsource (lib "eagle-import") (part "RESISTOR_0402"))
    )
    (comp (ref "R26")
      (value "0")
      (footprint "eagle-import:R0402")
      (fields (field (name "HOUSEPART") "YES") (field (name "MPN") "MF-RES-0402-0"))
      (libsource (lib "eagle-import") (part "RESISTOR_0402"))
    )
    (comp (ref "R27")
      (value "0")
      (footprint "eagle-import:R0402")
      (fields (field (name "HOUSEPART") "YES") (field (name "MPN") "MF-RES-0402-0"))
      (libsource (lib "eagle-import") (part "RESISTOR_0402"))
    )
    (comp (ref "R28")
      (value "0")
      (footprint "eagle-import:R0402")
      (fields (field (name "HOUSEPART") "YES") (field (name "MPN") "MF-RES-0402-0"))
      (libsource (lib "eagle-import") (part "RESISTOR_0402"))
    )
    (comp (ref "R29")
      (value "0")
      (footprint "eagle-import:R0402")
      (fields (field (name "HOUSEPART") "YES") (field (name "MPN") "MF-RES-0402-0"))
      (libsource (lib "eagle-import") (part "RESISTOR_0402"))
    )
    (comp (ref "R30")
      (value "0")
      (footprint "eagle-import:R0402")
      (fields (field (name "HOUSEPART") "YES") (field (name "MPN") "MF-RES-0402-0"))
      (libsource (lib "eagle-import") (part "RESISTOR_0402"))
    )
    (comp (ref "R31")
      (value "0")
      (footprint "eagle-import:R0402")
      (fields (field (name "HOUSEPART") "YES") (field (name "MPN") "MF-RES-0402-0"))
      (libsource (lib "eagle-import") (part "RESISTOR_0402"))
    )
    (comp (ref "REGOUT")
      (value "PAD24AWG_PAD")
      (footprint "eagle-import:24AWG_PAD")
      (libsource (lib "eagle-import") (part "PAD24AWG_PAD"))
    )
    (comp (ref "SPI0_CS0")
      (value "PAD24AWG_PAD")
      (footprint "eagle-import:24AWG_PAD")
      (libsource (lib "eagle-import") (part "PAD24AWG_PAD"))
    )
    (comp (ref "SPI0_MISO")
      (value "PAD24AWG_PAD")
      (footprint "eagle-import:24AWG_PAD")
      (libsource (lib "eagle-import") (part "PAD24AWG_PAD"))
    )
    (comp (ref "SPI0_MOSI")
      (value "PAD24AWG_PAD")
      (footprint "eagle-import:24AWG_PAD")
      (libsource (lib "eagle-import") (part "PAD24AWG_PAD"))
    )
    (comp (ref "SPI0_SCLK")
      (value "PAD24AWG_PAD")
      (footprint "eagle-import:24AWG_PAD")
      (libsource (lib "eagle-import") (part "PAD24AWG_PAD"))
    )
    (comp (ref "SPI1_CS0")
      (value "PAD24AWG_PAD")
      (footprint "eagle-import:24AWG_PAD")
      (libsource (lib "eagle-import") (part "PAD24AWG_PAD"))
    )
    (comp (ref "SPI1_CS1")
      (value "PAD24AWG_PAD")
      (footprint "eagle-import:24AWG_PAD")
      (libsource (lib "eagle-import") (part "PAD24AWG_PAD"))
    )
    (comp (ref "SPI1_MISO")
      (value "PAD24AWG_PAD")
      (footprint "eagle-import:24AWG_PAD")
      (libsource (lib "eagle-import") (part "PAD24AWG_PAD"))
    )
    (comp (ref "SPI1_MOSI")
      (value "PAD24AWG_PAD")
      (footprint "eagle-import:24AWG_PAD")
      (libsource (lib "eagle-import") (part "PAD24AWG_PAD"))
    )
    (comp (ref "SPI1_SCLK")
      (value "PAD24AWG_PAD")
      (footprint "eagle-import:24AWG_PAD")
      (libsource (lib "eagle-import") (part "PAD24AWG_PAD"))
    )
    (comp (ref "U1")
      (value "MAX17504ATP+T")
      (footprint "eagle-import:21-0140L_T2055-4_MXM")
      (fields (field (name "COPYRIGHT") "Copyright (C) 2018 Accelerated Designs. All rights reserved"))
      (libsource (lib "eagle-import") (part "MAX17504ATP+T"))
    )
    (comp (ref "U2")
      (value "DMMT5401")
      (footprint "eagle-import:SOT26")
      (fields (field (name "MF") "Didoes Incorporated") (field (name "MPN") "DMMT5401-7-F"))
      (libsource (lib "eagle-import") (part "DMMT5401"))
    )
    (comp (ref "U3")
      (value "DMG2305UX")
      (footprint "eagle-import:SOT23")
      (fields (field (name "MF") "Alpha & Omega") (field (name "MPN") "AO3415A"))
      (libsource (lib "eagle-import") (part "DMG2305UX"))
    )
    (comp (ref "U4")
      (value "STM32G474CEU6")
      (footprint "eagle-import:QFN50P700X700X60-49N")
      (fields (field (name "MOUSER_PART_NUMBER") "511-STM32G474CEU6") (field (name "MF") "ST"))
      (libsource (lib "eagle-import") (part "STM32G474CEU6"))
    )
    (comp (ref "U5")
      (value "LTC2875")
      (footprint "eagle-import:SOIC8")
      (fields (field (name "MF") "Analog") (field (name "MPN") "TCAN1057AEVDRQ1"))
      (libsource (lib "eagle-import") (part "LTC2875"))
    )
    (comp (ref "U6")
      (value "LTC2875")
      (footprint "eagle-import:SOIC8")
      (fields (field (name "MF") "Analog") (field (name "MPN") "TCAN1057AEVDRQ1"))
      (libsource (lib "eagle-import") (part "LTC2875"))
    )
    (comp (ref "U7")
      (value "STM32G474CEU6")
      (footprint "eagle-import:QFN50P700X700X60-49N")
      (fields (field (name "MOUSER_PART_NUMBER") "511-STM32G474CEU6") (field (name "MF") "ST"))
      (libsource (lib "eagle-import") (part "STM32G474CEU6"))
    )
    (comp (ref "U8")
      (value "BMI088LGA16")
      (footprint "eagle-import:LGA16")
      (fields (field (name "MF") "BOSCH") (field (name "MPN") "BMI088"))
      (libsource (lib "eagle-import") (part "BMI088LGA16"))
    )
    (comp (ref "U9")
      (value "LTC2875")
      (footprint "eagle-import:SOIC8")
      (fields (field (name "MF") "Analog") (field (name "MPN") "TCAN1057AEVDRQ1"))
      (libsource (lib "eagle-import") (part "LTC2875"))
    )
    (comp (ref "U10")
      (value "CAT24C32UDFN8")
      (footprint "eagle-import:UDFN8_2X3_ONS")
      (fields (field (name "MF") "ON Semiconductor") (field (name "MPN") "CAT24C32HU4I-GT3"))
      (libsource (lib "eagle-import") (part "CAT24C32UDFN8"))
    )
    (comp (ref "U11")
      (value "STM32G474CEU6")
      (footprint "eagle-import:QFN50P700X700X60-49N")
      (fields (field (name "MOUSER_PART_NUMBER") "511-STM32G474CEU6") (field (name "MF") "ST"))
      (libsource (lib "eagle-import") (part "STM32G474CEU6"))
    )
    (comp (ref "U12")
      (value "LTC2875")
      (footprint "eagle-import:SOIC8")
      (fields (field (name "MF") "Analog") (field (name "MPN") "TCAN1057AEVDRQ1"))
      (libsource (lib "eagle-import") (part "LTC2875"))
    )
    (comp (ref "U13")
      (value "LTC2875")
      (footprint "eagle-import:SOIC8")
      (fields (field (name "MF") "Analog") (field (name "MPN") "TCAN1057AEVDRQ1"))
      (libsource (lib "eagle-import") (part "LTC2875"))
    )
    (comp (ref "U14")
      (value "ICM-42688-P")
      (footprint "eagle-import:PQFN50P300X250X97-14N")
      (fields
        (field (name "DIGI-KEY_PART_NUMBER") "1428-ICM-42688-PCT-ND")
        (field (name "MF") "TDK InvenSense")
      )
      (libsource (lib "eagle-import") (part "ICM-42688-P"))
    )
    (comp (ref "UT")
      (value "PINHD-1X3")
      (footprint "eagle-import:1X03")
      (fields (field (name "MF") "MacroFab") (field (name "MPN") "MF-CON-2.54mm-01x03"))
      (libsource (lib "eagle-import") (part "PINHD-1X3"))
    )
    (comp (ref "V+")
      (value "PAD24AWG_PAD")
      (footprint "eagle-import:24AWG_PAD")
      (libsource (lib "eagle-import") (part "PAD24AWG_PAD"))
    )
  )
  (nets
    (net (code "1") (name "+3V3") (class "Default")
      (node (ref "3V3_TP") (pin "P$1") (pinfunction "P$1_P$1") (pintype "bidirectional"))
      (node (ref "C10") (pin "P$1") (pinfunction "P$1_P$1") (pintype "passive"))
      (node (ref "C11") (pin "P$1") (pinfunction "P$1_P$1") (pintype "passive"))
      (node (ref "C12") (pin "P$1") (pinfunction "P$1_P$1") (pintype "passive"))
      (node (ref "C13") (pin "P$1") (pinfunction "P$1_P$1") (pintype "passive"))
      (node (ref "C14") (pin "P$1") (pinfunction "P$1_P$1") (pintype "passive"))
      (node (ref "C15") (pin "P$1") (pinfunction "P$1_P$1") (pintype "passive"))
      (node (ref "C19") (pin "P$1") (pinfunction "P$1_P$1") (pintype "passive"))
      (node (ref "C20") (pin "P$1") (pinfunction "P$1_P$1") (pintype "passive"))
      (node (ref "C21") (pin "P$1") (pinfunction "P$1_P$1") (pintype "passive"))
      (node (ref "C22") (pin "P$1") (pinfunction "P$1_P$1") (pintype "passive"))
      (node (ref "C23") (pin "P$1") (pinfunction "P$1_P$1") (pintype "passive"))
      (node (ref "C24") (pin "P$1") (pinfunction "P$1_P$1") (pintype "passive"))
      (node (ref "C27") (pin "P$1") (pinfunction "P$1_P$1") (pintype "passive"))
      (node (ref "C28") (pin "P$1") (pinfunction "P$1_P$1") (pintype "passive"))
      (node (ref "C29") (pin "P$1") (pinfunction "P$1_P$1") (pintype "passive"))
      (node (ref "C30") (pin "P$1") (pinfunction "P$1_P$1") (pintype "passive"))
      (node (ref "C31") (pin "P$1") (pinfunction "P$1_P$1") (pintype "passive"))
      (node (ref "C33") (pin "P$1") (pinfunction "P$1_P$1") (pintype "passive"))
      (node (ref "C34") (pin "P$1") (pinfunction "P$1_P$1") (pintype "passive"))
      (node (ref "C35") (pin "P$1") (pinfunction "P$1_P$1") (pintype "passive"))
      (node (ref "C36") (pin "P$1") (pinfunction "P$1_P$1") (pintype "passive"))
      (node (ref "C37") (pin "P$1") (pinfunction "P$1_P$1") (pintype "passive"))
      (node (ref "C38") (pin "P$1") (pinfunction "P$1_P$1") (pintype "passive"))
      (node (ref "C41") (pin "P$1") (pinfunction "P$1_P$1") (pintype "passive"))
      (node (ref "C42") (pin "P$1") (pinfunction "P$1_P$1") (pintype "passive"))
      (node (ref "I2C") (pin "1") (pinfunction "1_1") (pintype "passive"))
      (node (ref "J4") (pin "1") (pinfunction "1_1") (pintype "passive"))
      (node (ref "J4") (pin "17") (pinfunction "17_17") (pintype "passive"))
      (node (ref "JD1") (pin "6") (pinfunction "6_6") (pintype "passive"))
      (node (ref "JD2") (pin "6") (pinfunction "6_6") (pintype "passive"))
      (node (ref "JD3") (pin "6") (pinfunction "6_6") (pintype "passive"))
      (node (ref "JP6") (pin "2") (pinfunction "2_2") (pintype "passive"))
      (node (ref "R11") (pin "P$1") (pinfunction "P$1_P$1") (pintype "passive"))
      (node (ref "R12") (pin "P$1") (pinfunction "P$1_P$1") (pintype "passive"))
      (node (ref "R14") (pin "P$1") (pinfunction "P$1_P$1") (pintype "passive"))
      (node (ref "R15") (pin "P$1") (pinfunction "P$1_P$1") (pintype "passive"))
      (node (ref "R16") (pin "P$1") (pinfunction "P$1_P$1") (pintype "passive"))
      (node (ref "R17") (pin "P$1") (pinfunction "P$1_P$1") (pintype "passive"))
      (node (ref "R18") (pin "P$1") (pinfunction "P$1_P$1") (pintype "passive"))
      (node (ref "R22") (pin "P$1") (pinfunction "P$1_P$1") (pintype "passive"))
      (node (ref "R25") (pin "P$1") (pinfunction "P$1_P$1") (pintype "passive"))
      (node (ref "R7") (pin "P$1") (pinfunction "P$1_P$1") (pintype "passive"))
      (node (ref "R8") (pin "P$1") (pinfunction "P$1_P$1") (pintype "passive"))
      (node (ref "U10") (pin "8") (pinfunction "VCC_8") (pintype "bidirectional"))
      (node (ref "U11") (pin "1") (pinfunction "VBAT_1") (pintype "bidirectional"))
      (node (ref "U11") (pin "20") (pinfunction "VREF+_20") (pintype "bidirectional"))
      (node (ref "U11") (pin "21") (pinfunction "VDDA_21") (pintype "bidirectional"))
      (node (ref "U11") (pin "23") (pinfunction "VDD_1_23") (pintype "bidirectional"))
      (node (ref "U11") (pin "35") (pinfunction "VDD_2_35") (pintype "bidirectional"))
      (node (ref "U11") (pin "4") (pinfunction "PC15-OSC32_OUT_4") (pintype "bidirectional"))
      (node (ref "U11") (pin "48") (pinfunction "VDD_3_48") (pintype "bidirectional"))
      (node (ref "U14") (pin "5") (pinfunction "VDDIO_5") (pintype "power_in"))
      (node (ref "U14") (pin "8") (pinfunction "VDD_8") (pintype "power_in"))
      (node (ref "U4") (pin "1") (pinfunction "VBAT_1") (pintype "bidirectional"))
      (node (ref "U4") (pin "20") (pinfunction "VREF+_20") (pintype "bidirectional"))
      (node (ref "U4") (pin "21") (pinfunction "VDDA_21") (pintype "bidirectional"))
      (node (ref "U4") (pin "23") (pinfunction "VDD_1_23") (pintype "bidirectional"))
      (node (ref "U4") (pin "35") (pinfunction "VDD_2_35") (pintype "bidirectional"))
      (node (ref "U4") (pin "48") (pinfunction "VDD_3_48") (pintype "bidirectional"))
      (node (ref "U7") (pin "1") (pinfunction "VBAT_1") (pintype "bidirectional"))
      (node (ref "U7") (pin "20") (pinfunction "VREF+_20") (pintype "bidirectional"))
      (node (ref "U7") (pin "21") (pinfunction "VDDA_21") (pintype "bidirectional"))
      (node (ref "U7") (pin "23") (pinfunction "VDD_1_23") (pintype "bidirectional"))
      (node (ref "U7") (pin "3") (pinfunction "PC14-OSC32_IN_3") (pintype "bidirectional"))
      (node (ref "U7") (pin "35") (pinfunction "VDD_2_35") (pintype "bidirectional"))
      (node (ref "U7") (pin "48") (pinfunction "VDD_3_48") (pintype "bidirectional"))
      (node (ref "U8") (pin "11") (pinfunction "VDDIO_11") (pintype "bidirectional"))
      (node (ref "U8") (pin "3") (pinfunction "VDD_3") (pintype "bidirectional"))
    )
    (net (code "2") (name "+5V") (class "Default")
      (node (ref "+5V") (pin "P$1") (pinfunction "P$1_P$1") (pintype "bidirectional"))
      (node (ref "J4") (pin "2") (pinfunction "2_2") (pintype "passive"))
      (node (ref "J4") (pin "4") (pinfunction "4_4") (pintype "passive"))
      (node (ref "JP6") (pin "1") (pinfunction "1_1") (pintype "passive"))
      (node (ref "R23") (pin "P$1") (pinfunction "P$1_P$1") (pintype "passive"))
      (node (ref "R4") (pin "P$1") (pinfunction "P$1_P$1") (pintype "passive"))
      (node (ref "U2") (pin "6") (pinfunction "E1_6") (pintype "bidirectional"))
      (node (ref "U3") (pin "3") (pinfunction "D_3") (pintype "passive"))
    )
    (net (code "3") (name "/5VSW") (class "Default")
      (node (ref "C5") (pin "P$2") (pinfunction "P$2_P$2") (pintype "passive"))
      (node (ref "L1") (pin "2") (pinfunction "2_2") (pintype "passive"))
      (node (ref "U1") (pin "17") (pinfunction "LX_2_17") (pintype "passive"))
      (node (ref "U1") (pin "18") (pinfunction "LX_3_18") (pintype "passive"))
      (node (ref "U1") (pin "19") (pinfunction "LX_19") (pintype "passive"))
    )
    (net (code "4") (name "/AUX_IRQ1") (class "Default")
      (node (ref "J4") (pin "15") (pinfunction "15_15") (pintype "passive"))
      (node (ref "U7") (pin "17") (pinfunction "PB0_17") (pintype "bidirectional"))
    )
    (net (code "5") (name "/AUX_IRQ2") (class "Default")
      (node (ref "J4") (pin "16") (pinfunction "16_16") (pintype "passive"))
      (node (ref "U7") (pin "18") (pinfunction "PB1_18") (pintype "bidirectional"))
    )
    (net (code "6") (name "/AUX_IRQ3") (class "Default")
      (node (ref "J4") (pin "18") (pinfunction "18_18") (pintype "passive"))
      (node (ref "U7") (pin "19") (pinfunction "PB2_19") (pintype "bidirectional"))
    )
    (net (code "7") (name "/CAN_VCC") (class "Default")
      (node (ref "C16") (pin "P$1") (pinfunction "P$1_P$1") (pintype "passive"))
      (node (ref "C17") (pin "P$1") (pinfunction "P$1_P$1") (pintype "passive"))
      (node (ref "C25") (pin "P$1") (pinfunction "P$1_P$1") (pintype "passive"))
      (node (ref "C39") (pin "P$1") (pinfunction "P$1_P$1") (pintype "passive"))
      (node (ref "C40") (pin "P$1") (pinfunction "P$1_P$1") (pintype "passive"))
      (node (ref "R22") (pin "P$2") (pinfunction "P$2_P$2") (pintype "passive"))
      (node (ref "R23") (pin "P$2") (pinfunction "P$2_P$2") (pintype "passive"))
      (node (ref "U12") (pin "3") (pinfunction "VCC_3") (pintype "power_in"))
      (node (ref "U13") (pin "3") (pinfunction "VCC_3") (pintype "power_in"))
      (node (ref "U5") (pin "3") (pinfunction "VCC_3") (pintype "power_in"))
      (node (ref "U6") (pin "3") (pinfunction "VCC_3") (pintype "power_in"))
      (node (ref "U9") (pin "3") (pinfunction "VCC_3") (pintype "power_in"))
    )
    (net (code "8") (name "/CAN_VIO") (class "Default")
      (node (ref "C26") (pin "P$1") (pinfunction "P$1_P$1") (pintype "passive"))
      (node (ref "C43") (pin "P$1") (pinfunction "P$1_P$1") (pintype "passive"))
      (node (ref "C44") (pin "P$1") (pinfunction "P$1_P$1") (pintype "passive"))
      (node (ref "C45") (pin "P$1") (pinfunction "P$1_P$1") (pintype "passive"))
      (node (ref "C46") (pin "P$1") (pinfunction "P$1_P$1") (pintype "passive"))
      (node (ref "R24") (pin "P$1") (pinfunction "P$1_P$1") (pintype "passive"))
      (node (ref "R25") (pin "P$2") (pinfunction "P$2_P$2") (pintype "passive"))
      (node (ref "U12") (pin "5") (pinfunction "SPLIT_5") (pintype "input"))
      (node (ref "U13") (pin "5") (pinfunction "SPLIT_5") (pintype "input"))
      (node (ref "U5") (pin "5") (pinfunction "SPLIT_5") (pintype "input"))
      (node (ref "U6") (pin "5") (pinfunction "SPLIT_5") (pintype "input"))
      (node (ref "U9") (pin "5") (pinfunction "SPLIT_5") (pintype "input"))
    )
    (net (code "9") (name "/I2C1_SCL") (class "Default")
      (node (ref "I2C") (pin "3") (pinfunction "3_3") (pintype "passive"))
      (node (ref "J4") (pin "5") (pinfunction "5_5") (pintype "passive"))
    )
    (net (code "10") (name "/I2C1_SDA") (class "Default")
      (node (ref "I2C") (pin "2") (pinfunction "2_2") (pintype "passive"))
      (node (ref "J4") (pin "3") (pinfunction "3_3") (pintype "passive"))
    )
    (net (code "11") (name "/ID_SCL") (class "Default")
      (node (ref "J4") (pin "28") (pinfunction "28_28") (pintype "passive"))
      (node (ref "R16") (pin "P$2") (pinfunction "P$2_P$2") (pintype "passive"))
      (node (ref "U10") (pin "6") (pinfunction "SCL_6") (pintype "bidirectional"))
    )
    (net (code "12") (name "/ID_SDA") (class "Default")
      (node (ref "J4") (pin "27") (pinfunction "27_27") (pintype "passive"))
      (node (ref "R15") (pin "P$2") (pinfunction "P$2_P$2") (pintype "passive"))
      (node (ref "U10") (pin "5") (pinfunction "SDA_5") (pintype "bidirectional"))
    )
    (net (code "13") (name "/IFACEA_IRQ1") (class "Default")
      (node (ref "J4") (pin "37") (pinfunction "37_37") (pintype "passive"))
      (node (ref "U4") (pin "17") (pinfunction "PB0_17") (pintype "bidirectional"))
    )
    (net (code "14") (name "/IFACEB_IRQ1") (class "Default")
      (node (ref "J4") (pin "29") (pinfunction "29_29") (pintype "passive"))
      (node (ref "U11") (pin "17") (pinfunction "PB0_17") (pintype "bidirectional"))
    )
    (net (code "15") (name "/IMU2_CLKIN") (class "Default")
      (node (ref "U14") (pin "9") (pinfunction "INT2/FSYNC/CLKIN_9") (pintype "bidirectional"))
      (node (ref "U7") (pin "22") (pinfunction "PB10_22") (pintype "bidirectional"))
    )
    (net (code "16") (name "/IMU2_CS") (class "Default")
      (node (ref "U14") (pin "12") (pinfunction "AP_CS_12") (pintype "input"))
      (node (ref "U7") (pin "24") (pinfunction "PB11_24") (pintype "bidirectional"))
    )
    (net (code "17") (name "/IMU_ACC_INT") (class "Default")
      (node (ref "U7") (pin "32") (pinfunction "PA10_32") (pintype "bidirectional"))
      (node (ref "U8") (pin "16") (pinfunction "INT1_16") (pintype "bidirectional"))
    )
    (net (code "18") (name "/IMU_CS1") (class "Default")
      (node (ref "U7") (pin "31") (pinfunction "PA9_31") (pintype "bidirectional"))
      (node (ref "U8") (pin "14") (pinfunction "CSB1_14") (pintype "bidirectional"))
    )
    (net (code "19") (name "/IMU_CS2") (class "Default")
      (node (ref "U7") (pin "25") (pinfunction "PB12_25") (pintype "bidirectional"))
      (node (ref "U8") (pin "5") (pinfunction "CSB2_5") (pintype "bidirectional"))
    )
    (net (code "20") (name "/IMU_GYRO_INT") (class "Default")
      (node (ref "U14") (pin "4") (pinfunction "INT1/INT_4") (pintype "output"))
      (node (ref "U7") (pin "30") (pinfunction "PA8_30") (pintype "bidirectional"))
      (node (ref "U8") (pin "12") (pinfunction "INT3_12") (pintype "bidirectional"))
    )
    (net (code "21") (name "/IMU_MISO") (class "Default")
      (node (ref "U14") (pin "1") (pinfunction "AP_SDO/AP_AD0_1") (pintype "bidirectional"))
      (node (ref "U7") (pin "27") (pinfunction "PB14_27") (pintype "bidirectional"))
      (node (ref "U8") (pin "10") (pinfunction "SDO2_10") (pintype "bidirectional"))
      (node (ref "U8") (pin "15") (pinfunction "SDO1_15") (pintype "bidirectional"))
    )
    (net (code "22") (name "/IMU_MOSI") (class "Default")
      (node (ref "U14") (pin "14") (pinfunction "AP_SDA/AP_SDIO/AP_SDI_14") (pintype "bidirectional"))
      (node (ref "U7") (pin "28") (pinfunction "PB15_28") (pintype "bidirectional"))
      (node (ref "U8") (pin "9") (pinfunction "SDI_9") (pintype "bidirectional"))
    )
    (net (code "23") (name "/IMU_SCK") (class "Default")
      (node (ref "U14") (pin "13") (pinfunction "AP_SCL/AP_SCLK_13") (pintype "input"))
      (node (ref "U7") (pin "26") (pinfunction "PB13_26") (pintype "bidirectional"))
      (node (ref "U8") (pin "8") (pinfunction "SCK_8") (pintype "bidirectional"))
    )
    (net (code "24") (name "/PI32") (class "Default")
      (node (ref "J4") (pin "32") (pinfunction "32_32") (pintype "passive"))
      (node (ref "UT") (pin "1") (pinfunction "1_1") (pintype "passive"))
    )
    (net (code "25") (name "/PI33") (class "Default")
      (node (ref "J4") (pin "33") (pinfunction "33_33") (pintype "passive"))
      (node (ref "UT") (pin "2") (pinfunction "2_2") (pintype "passive"))
    )
    (net (code "26") (name "/PI_RX_3V") (class "Default")
      (node (ref "J4") (pin "10") (pinfunction "10_10") (pintype "passive"))
    )
    (net (code "27") (name "/PI_TX_3V") (class "Default")
      (node (ref "J4") (pin "8") (pinfunction "8_8") (pintype "passive"))
    )
    (net (code "28") (name "/REGOUT") (class "Default")
      (node (ref "C7") (pin "P$1") (pinfunction "P$1_P$1") (pintype "passive"))
      (node (ref "C8") (pin "P$1") (pinfunction "P$1_P$1") (pintype "passive"))
      (node (ref "L1") (pin "1") (pinfunction "1_1") (pintype "passive"))
      (node (ref "R2") (pin "P$1") (pinfunction "P$1_P$1") (pintype "passive"))
      (node (ref "REGOUT") (pin "P$1") (pinfunction "P$1_P$1") (pintype "bidirectional"))
      (node (ref "U2") (pin "5") (pinfunction "E2_5") (pintype "bidirectional"))
      (node (ref "U3") (pin "2") (pinfunction "S_2") (pintype "passive"))
    )
    (net (code "29") (name "/SPI0_CS0") (class "Default")
      (node (ref "J4") (pin "24") (pinfunction "24_24") (pintype "passive"))
      (node (ref "SPI0_CS0") (pin "P$1") (pinfunction "P$1_P$1") (pintype "bidirectional"))
      (node (ref "U7") (pin "12") (pinfunction "PA4_12") (pintype "bidirectional"))
    )
    (net (code "30") (name "/SPI0_CS1") (class "Default")
      (node (ref "J4") (pin "26") (pinfunction "26_26") (pintype "passive"))
    )
    (net (code "31") (name "/SPI0_MISO") (class "Default")
      (node (ref "R30") (pin "P$1") (pinfunction "P$1_P$1") (pintype "passive"))
      (node (ref "SPI0_MISO") (pin "P$1") (pinfunction "P$1_P$1") (pintype "bidirectional"))
      (node (ref "U7") (pin "14") (pinfunction "PA6_14") (pintype "bidirectional"))
    )
    (net (code "32") (name "/SPI0_MOSI") (class "Default")
      (node (ref "R29") (pin "P$1") (pinfunction "P$1_P$1") (pintype "passive"))
      (node (ref "SPI0_MOSI") (pin "P$1") (pinfunction "P$1_P$1") (pintype "bidirectional"))
      (node (ref "U7") (pin "15") (pinfunction "PA7_15") (pintype "bidirectional"))
    )
    (net (code "33") (name "/SPI0_SCLK") (class "Default")
      (node (ref "R31") (pin "P$1") (pinfunction "P$1_P$1") (pintype "passive"))
      (node (ref "SPI0_SCLK") (pin "P$1") (pinfunction "P$1_P$1") (pintype "bidirectional"))
      (node (ref "U7") (pin "13") (pinfunction "PA5_13") (pintype "bidirectional"))
    )
    (net (code "34") (name "/SPI1_CS0") (class "Default")
      (node (ref "J4") (pin "12") (pinfunction "12_12") (pintype "passive"))
      (node (ref "SPI1_CS0") (pin "P$1") (pinfunction "P$1_P$1") (pintype "bidirectional"))
      (node (ref "U4") (pin "12") (pinfunction "PA4_12") (pintype "bidirectional"))
    )
    (net (code "35") (name "/SPI1_CS1") (class "Default")
      (node (ref "J4") (pin "11") (pinfunction "11_11") (pintype "passive"))
      (node (ref "SPI1_CS1") (pin "P$1") (pinfunction "P$1_P$1") (pintype "bidirectional"))
      (node (ref "U11") (pin "12") (pinfunction "PA4_12") (pintype "bidirectional"))
    )
    (net (code "36") (name "/SPI1_CS2") (class "Default")
      (node (ref "J4") (pin "36") (pinfunction "36_36") (pintype "passive"))
    )
    (net (code "37") (name "/SPI1_MISO") (class "Default")
      (node (ref "R28") (pin "P$1") (pinfunction "P$1_P$1") (pintype "passive"))
      (node (ref "SPI1_MISO") (pin "P$1") (pinfunction "P$1_P$1") (pintype "bidirectional"))
      (node (ref "U11") (pin "14") (pinfunction "PA6_14") (pintype "bidirectional"))
      (node (ref "U4") (pin "14") (pinfunction "PA6_14") (pintype "bidirectional"))
    )
    (net (code "38") (name "/SPI1_MOSI") (class "Default")
      (node (ref "R26") (pin "P$2") (pinfunction "P$2_P$2") (pintype "passive"))
      (node (ref "SPI1_MOSI") (pin "P$1") (pinfunction "P$1_P$1") (pintype "bidirectional"))
      (node (ref "U11") (pin "15") (pinfunction "PA7_15") (pintype "bidirectional"))
      (node (ref "U4") (pin "15") (pinfunction "PA7_15") (pintype "bidirectional"))
    )
    (net (code "39") (name "/SPI1_SCLK") (class "Default")
      (node (ref "R27") (pin "P$2") (pinfunction "P$2_P$2") (pintype "passive"))
      (node (ref "SPI1_SCLK") (pin "P$1") (pinfunction "P$1_P$1") (pintype "bidirectional"))
      (node (ref "U11") (pin "13") (pinfunction "PA5_13") (pintype "bidirectional"))
      (node (ref "U4") (pin "13") (pinfunction "PA5_13") (pintype "bidirectional"))
    )
    (net (code "40") (name "/V+") (class "Default")
      (node (ref "F1") (pin "1") (pinfunction "1_1") (pintype "passive"))
      (node (ref "J1") (pin "2") (pinfunction "2_2") (pintype "passive"))
      (node (ref "J2") (pin "2") (pinfunction "2_2") (pintype "passive"))
      (node (ref "R21") (pin "P$1") (pinfunction "P$1_P$1") (pintype "passive"))
      (node (ref "V+") (pin "P$1") (pinfunction "P$1_P$1") (pintype "bidirectional"))
    )
    (net (code "41") (name "/V+FUSED") (class "Default")
      (node (ref "C1") (pin "P$1") (pinfunction "P$1_P$1") (pintype "passive"))
      (node (ref "C2") (pin "P$1") (pinfunction "P$1_P$1") (pintype "passive"))
      (node (ref "C3") (pin "P$1") (pinfunction "P$1_P$1") (pintype "passive"))
      (node (ref "D12") (pin "C") (pinfunction "C_C") (pintype "bidirectional"))
      (node (ref "F1") (pin "2") (pinfunction "2_2") (pintype "passive"))
      (node (ref "U1") (pin "1") (pinfunction "VIN_2_1") (pintype "passive"))
      (node (ref "U1") (pin "2") (pinfunction "VIN_3_2") (pintype "passive"))
      (node (ref "U1") (pin "3") (pinfunction "VIN_3") (pintype "passive"))
      (node (ref "U1") (pin "4") (pinfunction "EN/UVLO_4") (pintype "passive"))
    )
    (net (code "42") (name "/V+SENSE") (class "Default")
      (node (ref "R1") (pin "P$1") (pinfunction "P$1_P$1") (pintype "passive"))
      (node (ref "R21") (pin "P$2") (pinfunction "P$2_P$2") (pintype "passive"))
      (node (ref "U7") (pin "16") (pinfunction "PC4_16") (pintype "bidirectional"))
    )
    (net (code "43") (name "GND") (class "Default")
      (node (ref "C1") (pin "P$2") (pinfunction "P$2_P$2") (pintype "passive"))
      (node (ref "C10") (pin "P$2") (pinfunction "P$2_P$2") (pintype "passive"))
      (node (ref "C11") (pin "P$2") (pinfunction "P$2_P$2") (pintype "passive"))
      (node (ref "C12") (pin "P$2") (pinfunction "P$2_P$2") (pintype "passive"))
      (node (ref "C13") (pin "P$2") (pinfunction "P$2_P$2") (pintype "passive"))
      (node (ref "C14") (pin "P$2") (pinfunction "P$2_P$2") (pintype "passive"))
      (node (ref "C15") (pin "P$2") (pinfunction "P$2_P$2") (pintype "passive"))
      (node (ref "C16") (pin "P$2") (pinfunction "P$2_P$2") (pintype "passive"))
      (node (ref "C17") (pin "P$2") (pinfunction "P$2_P$2") (pintype "passive"))
      (node (ref "C18") (pin "P$2") (pinfunction "P$2_P$2") (pintype "passive"))
      (node (ref "C19") (pin "P$2") (pinfunction "P$2_P$2") (pintype "passive"))
      (node (ref "C2") (pin "P$2") (pinfunction "P$2_P$2") (pintype "passive"))
      (node (ref "C20") (pin "P$2") (pinfunction "P$2_P$2") (pintype "passive"))
      (node (ref "C21") (pin "P$2") (pinfunction "P$2_P$2") (pintype "passive"))
      (node (ref "C22") (pin "P$2") (pinfunction "P$2_P$2") (pintype "passive"))
      (node (ref "C23") (pin "P$2") (pinfunction "P$2_P$2") (pintype "passive"))
      (node (ref "C24") (pin "P$2") (pinfunction "P$2_P$2") (pintype "passive"))
      (node (ref "C25") (pin "P$2") (pinfunction "P$2_P$2") (pintype "passive"))
      (node (ref "C26") (pin "P$2") (pinfunction "P$2_P$2") (pintype "passive"))
      (node (ref "C27") (pin "P$2") (pinfunction "P$2_P$2") (pintype "passive"))
      (node (ref "C28") (pin "P$2") (pinfunction "P$2_P$2") (pintype "passive"))
      (node (ref "C29") (pin "P$2") (pinfunction "P$2_P$2") (pintype "passive"))
      (node (ref "C3") (pin "P$2") (pinfunction "P$2_P$2") (pintype "passive"))
      (node (ref "C30") (pin "P$2") (pinfunction "P$2_P$2") (pintype "passive"))
      (node (ref "C31") (pin "P$2") (pinfunction "P$2_P$2") (pintype "passive"))
      (node (ref "C32") (pin "P$2") (pinfunction "P$2_P$2") (pintype "passive"))
      (node (ref "C33") (pin "P$2") (pinfunction "P$2_P$2") (pintype "passive"))
      (node (ref "C34") (pin "P$2") (pinfunction "P$2_P$2") (pintype "passive"))
      (node (ref "C35") (pin "P$2") (pinfunction "P$2_P$2") (pintype "passive"))
      (node (ref "C36") (pin "P$2") (pinfunction "P$2_P$2") (pintype "passive"))
      (node (ref "C37") (pin "P$2") (pinfunction "P$2_P$2") (pintype "passive"))
      (node (ref "C38") (pin "P$2") (pinfunction "P$2_P$2") (pintype "passive"))
      (node (ref "C39") (pin "P$2") (pinfunction "P$2_P$2") (pintype "passive"))
      (node (ref "C4") (pin "P$2") (pinfunction "P$2_P$2") (pintype "passive"))
      (node (ref "C40") (pin "P$2") (pinfunction "P$2_P$2") (pintype "passive"))
      (node (ref "C41") (pin "P$2") (pinfunction "P$2_P$2") (pintype "passive"))
      (node (ref "C42") (pin "P$2") (pinfunction "P$2_P$2") (pintype "passive"))
      (node (ref "C43") (pin "P$2") (pinfunction "P$2_P$2") (pintype "passive"))
      (node (ref "C44") (pin "P$2") (pinfunction "P$2_P$2") (pintype "passive"))
      (node (ref "C45") (pin "P$2") (pinfunction "P$2_P$2") (pintype "passive"))
      (node (ref "C46") (pin "P$2") (pinfunction "P$2_P$2") (pintype "passive"))
      (node (ref "C6") (pin "P$2") (pinfunction "P$2_P$2") (pintype "passive"))
      (node (ref "C7") (pin "P$2") (pinfunction "P$2_P$2") (pintype "passive"))
      (node (ref "C8") (pin "P$2") (pinfunction "P$2_P$2") (pintype "passive"))
      (node (ref "C9") (pin "P$2") (pinfunction "P$2_P$2") (pintype "passive"))
      (node (ref "D1") (pin "CATHODE") (pinfunction "CATHODE_CATHODE") (pintype "power_in"))
      (node (ref "D12") (pin "A") (pinfunction "A_A") (pintype "bidirectional"))
      (node (ref "GND") (pin "P$1") (pinfunction "P$1_P$1") (pintype "bidirectional"))
      (node (ref "I2C") (pin "4") (pinfunction "4_4") (pintype "passive"))
      (node (ref "J1") (pin "1") (pinfunction "1_1") (pintype "passive"))
      (node (ref "J2") (pin "1") (pinfunction "1_1") (pintype "passive"))
      (node (ref "J4") (pin "14") (pinfunction "14_14") (pintype "passive"))
      (node (ref "J4") (pin "20") (pinfunction "20_20") (pintype "passive"))
      (node (ref "J4") (pin "25") (pinfunction "25_25") (pintype "passive"))
      (node (ref "J4") (pin "30") (pinfunction "30_30") (pintype "passive"))
      (node (ref "J4") (pin "34") (pinfunction "34_34") (pintype "passive"))
      (node (ref "J4") (pin "39") (pinfunction "39_39") (pintype "passive"))
      (node (ref "J4") (pin "6") (pinfunction "6_6") (pintype "passive"))
      (node (ref "J4") (pin "9") (pinfunction "9_9") (pintype "passive"))
      (node (ref "JC1") (pin "3") (pinfunction "3_3") (pintype "passive"))
      (node (ref "JC2") (pin "3") (pinfunction "3_3") (pintype "passive"))
      (node (ref "JC3") (pin "3") (pinfunction "3_3") (pintype "passive"))
      (node (ref "JC4") (pin "3") (pinfunction "3_3") (pintype "passive"))
      (node (ref "JC5") (pin "3") (pinfunction "3_3") (pintype "passive"))
      (node (ref "JD1") (pin "4") (pinfunction "4_4") (pintype "passive"))
      (node (ref "JD2") (pin "4") (pinfunction "4_4") (pintype "passive"))
      (node (ref "JD3") (pin "4") (pinfunction "4_4") (pintype "passive"))
      (node (ref "JP6") (pin "3") (pinfunction "3_3") (pintype "passive"))
      (node (ref "JP7") (pin "1") (pinfunction "1_1") (pintype "passive"))
      (node (ref "R1") (pin "P$2") (pinfunction "P$2_P$2") (pintype "passive"))
      (node (ref "R24") (pin "P$2") (pinfunction "P$2_P$2") (pintype "passive"))
      (node (ref "R3") (pin "P$2") (pinfunction "P$2_P$2") (pintype "passive"))
      (node (ref "R5") (pin "P$2") (pinfunction "P$2_P$2") (pintype "passive"))
      (node (ref "R6") (pin "P$2") (pinfunction "P$2_P$2") (pintype "passive"))
      (node (ref "U1") (pin "13") (pinfunction "SGND_13") (pintype "passive"))
      (node (ref "U1") (pin "14") (pinfunction "PGND_2_14") (pintype "passive"))
      (node (ref "U1") (pin "15") (pinfunction "PGND_3_15") (pintype "passive"))
      (node (ref "U1") (pin "16") (pinfunction "PGND_16") (pintype "passive"))
      (node (ref "U1") (pin "21") (pinfunction "EPAD_21") (pintype "passive"))
      (node (ref "U1") (pin "22") (pinfunction "EPAD_22") (pintype "passive"))
      (node (ref "U1") (pin "23") (pinfunction "EPAD_23") (pintype "passive"))
      (node (ref "U1") (pin "24") (pinfunction "EPAD_24") (pintype "passive"))
      (node (ref "U1") (pin "25") (pinfunction "EPAD_25") (pintype "passive"))
      (node (ref "U1") (pin "26") (pinfunction "EPAD_26") (pintype "passive"))
      (node (ref "U1") (pin "27") (pinfunction "EPAD_27") (pintype "passive"))
      (node (ref "U1") (pin "28") (pinfunction "EPAD_28") (pintype "passive"))
      (node (ref "U1") (pin "29") (pinfunction "EPAD_29") (pintype "passive"))
      (node (ref "U1") (pin "30") (pinfunction "EPAD_30") (pintype "passive"))
      (node (ref "U10") (pin "1") (pinfunction "A0_1") (pintype "bidirectional"))
      (node (ref "U10") (pin "2") (pinfunction "A1_2") (pintype "bidirectional"))
      (node (ref "U10") (pin "3") (pinfunction "A2_3") (pintype "bidirectional"))
      (node (ref "U10") (pin "4") (pinfunction "VSS_4") (pintype "bidirectional"))
      (node (ref "U11") (pin "3") (pinfunction "PC14-OSC32_IN_3") (pintype "bidirectional"))
      (node (ref "U11") (pin "49") (pinfunction "THERMALPAD_49") (pintype "bidirectional"))
      (node (ref "U12") (pin "2") (pinfunction "GND_2") (pintype "power_in"))
      (node (ref "U12") (pin "8") (pinfunction "RS_8") (pintype "input"))
      (node (ref "U13") (pin "2") (pinfunction "GND_2") (pintype "power_in"))
      (node (ref "U13") (pin "8") (pinfunction "RS_8") (pintype "input"))
      (node (ref "U14") (pin "6") (pinfunction "GND_6") (pintype "power_in"))
      (node (ref "U4") (pin "3") (pinfunction "PC14-OSC32_IN_3") (pintype "bidirectional"))
      (node (ref "U4") (pin "4") (pinfunction "PC15-OSC32_OUT_4") (pintype "bidirectional"))
      (node (ref "U4") (pin "49") (pinfunction "THERMALPAD_49") (pintype "bidirectional"))
      (node (ref "U5") (pin "2") (pinfunction "GND_2") (pintype "power_in"))
      (node (ref "U5") (pin "8") (pinfunction "RS_8") (pintype "input"))
      (node (ref "U6") (pin "2") (pinfunction "GND_2") (pintype "power_in"))
      (node (ref "U6") (pin "8") (pinfunction "RS_8") (pintype "input"))
      (node (ref "U7") (pin "4") (pinfunction "PC15-OSC32_OUT_4") (pintype "bidirectional"))
      (node (ref "U7") (pin "49") (pinfunction "THERMALPAD_49") (pintype "bidirectional"))
      (node (ref "U8") (pin "4") (pinfunction "GND_4") (pintype "bidirectional"))
      (node (ref "U8") (pin "6") (pinfunction "GNDIO_6") (pintype "bidirectional"))
      (node (ref "U8") (pin "7") (pinfunction "PS_7") (pintype "bidirectional"))
      (node (ref "U9") (pin "2") (pinfunction "GND_2") (pintype "power_in"))
      (node (ref "U9") (pin "8") (pinfunction "RS_8") (pintype "input"))
      (node (ref "UT") (pin "3") (pinfunction "3_3") (pintype "passive"))
    )
    (net (code "44") (name "Net-(D1-PadANODE)") (class "Default")
      (node (ref "D1") (pin "ANODE") (pinfunction "ANODE_ANODE") (pintype "power_in"))
      (node (ref "R4") (pin "P$2") (pinfunction "P$2_P$2") (pintype "passive"))
    )
    (net (code "45") (name "Net-(D2-PadANODE)") (class "Default")
      (node (ref "D2") (pin "ANODE") (pinfunction "ANODE_ANODE") (pintype "power_in"))
      (node (ref "R7") (pin "P$2") (pinfunction "P$2_P$2") (pintype "passive"))
    )
    (net (code "46") (name "Net-(D3-PadANODE)") (class "Default")
      (node (ref "D3") (pin "ANODE") (pinfunction "ANODE_ANODE") (pintype "power_in"))
      (node (ref "R8") (pin "P$2") (pinfunction "P$2_P$2") (pintype "passive"))
    )
    (net (code "47") (name "Net-(D4-PadANODE)") (class "Default")
      (node (ref "D4") (pin "ANODE") (pinfunction "ANODE_ANODE") (pintype "power_in"))
      (node (ref "R11") (pin "P$2") (pinfunction "P$2_P$2") (pintype "passive"))
    )
    (net (code "48") (name "Net-(D5-PadANODE)") (class "Default")
      (node (ref "D5") (pin "ANODE") (pinfunction "ANODE_ANODE") (pintype "power_in"))
      (node (ref "R12") (pin "P$2") (pinfunction "P$2_P$2") (pintype "passive"))
    )
    (net (code "49") (name "Net-(D6-PadANODE)") (class "Default")
      (node (ref "D6") (pin "ANODE") (pinfunction "ANODE_ANODE") (pintype "power_in"))
      (node (ref "R17") (pin "P$2") (pinfunction "P$2_P$2") (pintype "passive"))
    )
    (net (code "50") (name "Net-(D7-PadANODE)") (class "Default")
      (node (ref "D7") (pin "ANODE") (pinfunction "ANODE_ANODE") (pintype "power_in"))
      (node (ref "R18") (pin "P$2") (pinfunction "P$2_P$2") (pintype "passive"))
    )
    (net (code "51") (name "Net-(J4-Pad19)") (class "Default")
      (node (ref "J4") (pin "19") (pinfunction "19_19") (pintype "passive"))
      (node (ref "R29") (pin "P$2") (pinfunction "P$2_P$2") (pintype "passive"))
    )
    (net (code "52") (name "Net-(J4-Pad21)") (class "Default")
      (node (ref "J4") (pin "21") (pinfunction "21_21") (pintype "passive"))
      (node (ref "R30") (pin "P$2") (pinfunction "P$2_P$2") (pintype "passive"))
    )
    (net (code "53") (name "Net-(J4-Pad23)") (class "Default")
      (node (ref "J4") (pin "23") (pinfunction "23_23") (pintype "passive"))
      (node (ref "R31") (pin "P$2") (pinfunction "P$2_P$2") (pintype "passive"))
    )
    (net (code "54") (name "Net-(J4-Pad35)") (class "Default")
      (node (ref "J4") (pin "35") (pinfunction "35_35") (pintype "passive"))
      (node (ref "R28") (pin "P$2") (pinfunction "P$2_P$2") (pintype "passive"))
    )
    (net (code "55") (name "Net-(J4-Pad38)") (class "Default")
      (node (ref "J4") (pin "38") (pinfunction "38_38") (pintype "passive"))
      (node (ref "R26") (pin "P$1") (pinfunction "P$1_P$1") (pintype "passive"))
    )
    (net (code "56") (name "Net-(J4-Pad40)") (class "Default")
      (node (ref "J4") (pin "40") (pinfunction "40_40") (pintype "passive"))
      (node (ref "R27") (pin "P$1") (pinfunction "P$1_P$1") (pintype "passive"))
    )
    (net (code "57") (name "Net-(U1-BST)") (class "Default")
      (node (ref "C5") (pin "P$1") (pinfunction "P$1_P$1") (pintype "passive"))
      (node (ref "U1") (pin "20") (pinfunction "BST_20") (pintype "passive"))
    )
    (net (code "58") (name "Net-(U1-FB)") (class "Default")
      (node (ref "R2") (pin "P$2") (pinfunction "P$2_P$2") (pintype "passive"))
      (node (ref "R3") (pin "P$1") (pinfunction "P$1_P$1") (pintype "passive"))
      (node (ref "U1") (pin "9") (pinfunction "FB_9") (pintype "passive"))
    )
    (net (code "59") (name "Net-(U1-SS)") (class "Default")
      (node (ref "C4") (pin "P$1") (pinfunction "P$1_P$1") (pintype "passive"))
      (node (ref "U1") (pin "7") (pinfunction "SS_7") (pintype "passive"))
    )
    (net (code "60") (name "Net-(U1-VCC)") (class "Default")
      (node (ref "C6") (pin "P$1") (pinfunction "P$1_P$1") (pintype "passive"))
      (node (ref "U1") (pin "12") (pinfunction "VCC_12") (pintype "power_in"))
    )
    (net (code "61") (name "Net-(U2-B1)") (class "Default")
      (node (ref "R5") (pin "P$1") (pinfunction "P$1_P$1") (pintype "passive"))
      (node (ref "U2") (pin "2") (pinfunction "B1_2") (pintype "bidirectional"))
      (node (ref "U2") (pin "3") (pinfunction "B2_3") (pintype "bidirectional"))
      (node (ref "U2") (pin "4") (pinfunction "C2_4") (pintype "bidirectional"))
    )
    (net (code "62") (name "Net-(U2-C1)") (class "Default")
      (node (ref "R6") (pin "P$1") (pinfunction "P$1_P$1") (pintype "passive"))
      (node (ref "U2") (pin "1") (pinfunction "C1_1") (pintype "bidirectional"))
      (node (ref "U3") (pin "1") (pinfunction "G_1") (pintype "passive"))
    )
    (net (code "63") (name "Net-(U4-PA11)") (class "Default")
      (node (ref "U4") (pin "33") (pinfunction "PA11_33") (pintype "bidirectional"))
      (node (ref "U5") (pin "4") (pinfunction "RXD_4") (pintype "output"))
    )
    (net (code "64") (name "Net-(U4-PA12)") (class "Default")
      (node (ref "U4") (pin "34") (pinfunction "PA12_34") (pintype "bidirectional"))
      (node (ref "U5") (pin "1") (pinfunction "TXD_1") (pintype "input"))
    )
    (net (code "65") (name "Net-(U4-PA13)") (class "Default")
      (node (ref "JD1") (pin "3") (pinfunction "3_3") (pintype "passive"))
      (node (ref "U4") (pin "36") (pinfunction "PA13_36") (pintype "bidirectional"))
    )
    (net (code "66") (name "Net-(U4-PA14)") (class "Default")
      (node (ref "JD1") (pin "5") (pinfunction "5_5") (pintype "passive"))
      (node (ref "U4") (pin "37") (pinfunction "PA14_37") (pintype "bidirectional"))
    )
    (net (code "67") (name "Net-(U4-PB3)") (class "Default")
      (node (ref "U4") (pin "41") (pinfunction "PB3_41") (pintype "bidirectional"))
      (node (ref "U6") (pin "4") (pinfunction "RXD_4") (pintype "output"))
    )
    (net (code "68") (name "Net-(U4-PB4)") (class "Default")
      (node (ref "U4") (pin "42") (pinfunction "PB4_42") (pintype "bidirectional"))
      (node (ref "U6") (pin "1") (pinfunction "TXD_1") (pintype "input"))
    )
    (net (code "69") (name "Net-(U4-PF0-OSC_IN)") (class "Default")
      (node (ref "D3") (pin "CATHODE") (pinfunction "CATHODE_CATHODE") (pintype "power_in"))
      (node (ref "U4") (pin "5") (pinfunction "PF0-OSC_IN_5") (pintype "bidirectional"))
    )
    (net (code "70") (name "Net-(U4-PF1-OSC_OUT)") (class "Default")
      (node (ref "D2") (pin "CATHODE") (pinfunction "CATHODE_CATHODE") (pintype "power_in"))
      (node (ref "U4") (pin "6") (pinfunction "PF1-OSC_OUT_6") (pintype "bidirectional"))
    )
    (net (code "71") (name "Net-(U4-PG10-NRST)") (class "Default")
      (node (ref "C9") (pin "P$1") (pinfunction "P$1_P$1") (pintype "passive"))
      (node (ref "JD1") (pin "2") (pinfunction "2_2") (pintype "passive"))
      (node (ref "U4") (pin "7") (pinfunction "PG10-NRST_7") (pintype "bidirectional"))
    )
    (net (code "72") (name "Net-(U5-CANH)") (class "Default")
      (node (ref "JC2") (pin "1") (pinfunction "1_1") (pintype "passive"))
      (node (ref "R10") (pin "P$1") (pinfunction "P$1_P$1") (pintype "passive"))
      (node (ref "U5") (pin "7") (pinfunction "CANH_7") (pintype "bidirectional"))
    )
    (net (code "73") (name "Net-(U5-CANL)") (class "Default")
      (node (ref "JC2") (pin "2") (pinfunction "2_2") (pintype "passive"))
      (node (ref "R10") (pin "P$2") (pinfunction "P$2_P$2") (pintype "passive"))
      (node (ref "U5") (pin "6") (pinfunction "CANL_6") (pintype "bidirectional"))
    )
    (net (code "74") (name "Net-(U6-CANH)") (class "Default")
      (node (ref "JC1") (pin "1") (pinfunction "1_1") (pintype "passive"))
      (node (ref "R9") (pin "P$1") (pinfunction "P$1_P$1") (pintype "passive"))
      (node (ref "U6") (pin "7") (pinfunction "CANH_7") (pintype "bidirectional"))
    )
    (net (code "75") (name "Net-(U6-CANL)") (class "Default")
      (node (ref "JC1") (pin "2") (pinfunction "2_2") (pintype "passive"))
      (node (ref "R9") (pin "P$2") (pinfunction "P$2_P$2") (pintype "passive"))
      (node (ref "U6") (pin "6") (pinfunction "CANL_6") (pintype "bidirectional"))
    )
    (net (code "76") (name "Net-(U7-PA11)") (class "Default")
      (node (ref "U7") (pin "33") (pinfunction "PA11_33") (pintype "bidirectional"))
      (node (ref "U9") (pin "4") (pinfunction "RXD_4") (pintype "output"))
    )
    (net (code "77") (name "Net-(U7-PA12)") (class "Default")
      (node (ref "U7") (pin "34") (pinfunction "PA12_34") (pintype "bidirectional"))
      (node (ref "U9") (pin "1") (pinfunction "TXD_1") (pintype "input"))
    )
    (net (code "78") (name "Net-(U7-PA13)") (class "Default")
      (node (ref "JD3") (pin "3") (pinfunction "3_3") (pintype "passive"))
      (node (ref "U7") (pin "36") (pinfunction "PA13_36") (pintype "bidirectional"))
    )
    (net (code "79") (name "Net-(U7-PA14)") (class "Default")
      (node (ref "JD3") (pin "5") (pinfunction "5_5") (pintype "passive"))
      (node (ref "U7") (pin "37") (pinfunction "PA14_37") (pintype "bidirectional"))
    )
    (net (code "80") (name "Net-(U7-PF0-OSC_IN)") (class "Default")
      (node (ref "D5") (pin "CATHODE") (pinfunction "CATHODE_CATHODE") (pintype "power_in"))
      (node (ref "U7") (pin "5") (pinfunction "PF0-OSC_IN_5") (pintype "bidirectional"))
    )
    (net (code "81") (name "Net-(U7-PF1-OSC_OUT)") (class "Default")
      (node (ref "D4") (pin "CATHODE") (pinfunction "CATHODE_CATHODE") (pintype "power_in"))
      (node (ref "U7") (pin "6") (pinfunction "PF1-OSC_OUT_6") (pintype "bidirectional"))
    )
    (net (code "82") (name "Net-(U7-PG10-NRST)") (class "Default")
      (node (ref "C18") (pin "P$1") (pinfunction "P$1_P$1") (pintype "passive"))
      (node (ref "JD3") (pin "2") (pinfunction "2_2") (pintype "passive"))
      (node (ref "U7") (pin "7") (pinfunction "PG10-NRST_7") (pintype "bidirectional"))
    )
    (net (code "83") (name "Net-(U9-CANH)") (class "Default")
      (node (ref "JC5") (pin "1") (pinfunction "1_1") (pintype "passive"))
      (node (ref "R13") (pin "P$1") (pinfunction "P$1_P$1") (pintype "passive"))
      (node (ref "U9") (pin "7") (pinfunction "CANH_7") (pintype "bidirectional"))
    )
    (net (code "84") (name "Net-(U9-CANL)") (class "Default")
      (node (ref "JC5") (pin "2") (pinfunction "2_2") (pintype "passive"))
      (node (ref "R13") (pin "P$2") (pinfunction "P$2_P$2") (pintype "passive"))
      (node (ref "U9") (pin "6") (pinfunction "CANL_6") (pintype "bidirectional"))
    )
    (net (code "85") (name "Net-(U10-WP)") (class "Default")
      (node (ref "JP8") (pin "1") (pinfunction "1_1") (pintype "passive"))
      (node (ref "R14") (pin "P$2") (pinfunction "P$2_P$2") (pintype "passive"))
      (node (ref "U10") (pin "7") (pinfunction "WP_7") (pintype "bidirectional"))
    )
    (net (code "86") (name "Net-(U11-PA11)") (class "Default")
      (node (ref "U11") (pin "33") (pinfunction "PA11_33") (pintype "bidirectional"))
      (node (ref "U13") (pin "4") (pinfunction "RXD_4") (pintype "output"))
    )
    (net (code "87") (name "Net-(U11-PA12)") (class "Default")
      (node (ref "U11") (pin "34") (pinfunction "PA12_34") (pintype "bidirectional"))
      (node (ref "U13") (pin "1") (pinfunction "TXD_1") (pintype "input"))
    )
    (net (code "88") (name "Net-(U11-PA13)") (class "Default")
      (node (ref "JD2") (pin "3") (pinfunction "3_3") (pintype "passive"))
      (node (ref "U11") (pin "36") (pinfunction "PA13_36") (pintype "bidirectional"))
    )
    (net (code "89") (name "Net-(U11-PA14)") (class "Default")
      (node (ref "JD2") (pin "5") (pinfunction "5_5") (pintype "passive"))
      (node (ref "U11") (pin "37") (pinfunction "PA14_37") (pintype "bidirectional"))
    )
    (net (code "90") (name "Net-(U11-PB3)") (class "Default")
      (node (ref "U11") (pin "41") (pinfunction "PB3_41") (pintype "bidirectional"))
      (node (ref "U12") (pin "4") (pinfunction "RXD_4") (pintype "output"))
    )
    (net (code "91") (name "Net-(U11-PB4)") (class "Default")
      (node (ref "U11") (pin "42") (pinfunction "PB4_42") (pintype "bidirectional"))
      (node (ref "U12") (pin "1") (pinfunction "TXD_1") (pintype "input"))
    )
    (net (code "92") (name "Net-(U11-PF0-OSC_IN)") (class "Default")
      (node (ref "D7") (pin "CATHODE") (pinfunction "CATHODE_CATHODE") (pintype "power_in"))
      (node (ref "U11") (pin "5") (pinfunction "PF0-OSC_IN_5") (pintype "bidirectional"))
    )
    (net (code "93") (name "Net-(U11-PF1-OSC_OUT)") (class "Default")
      (node (ref "D6") (pin "CATHODE") (pinfunction "CATHODE_CATHODE") (pintype "power_in"))
      (node (ref "U11") (pin "6") (pinfunction "PF1-OSC_OUT_6") (pintype "bidirectional"))
    )
    (net (code "94") (name "Net-(U11-PG10-NRST)") (class "Default")
      (node (ref "C32") (pin "P$1") (pinfunction "P$1_P$1") (pintype "passive"))
      (node (ref "JD2") (pin "2") (pinfunction "2_2") (pintype "passive"))
      (node (ref "U11") (pin "7") (pinfunction "PG10-NRST_7") (pintype "bidirectional"))
    )
    (net (code "95") (name "Net-(U12-CANH)") (class "Default")
      (node (ref "JC3") (pin "1") (pinfunction "1_1") (pintype "passive"))
      (node (ref "R19") (pin "P$1") (pinfunction "P$1_P$1") (pintype "passive"))
      (node (ref "U12") (pin "7") (pinfunction "CANH_7") (pintype "bidirectional"))
    )
    (net (code "96") (name "Net-(U12-CANL)") (class "Default")
      (node (ref "JC3") (pin "2") (pinfunction "2_2") (pintype "passive"))
      (node (ref "R19") (pin "P$2") (pinfunction "P$2_P$2") (pintype "passive"))
      (node (ref "U12") (pin "6") (pinfunction "CANL_6") (pintype "bidirectional"))
    )
    (net (code "97") (name "Net-(U13-CANH)") (class "Default")
      (node (ref "JC4") (pin "1") (pinfunction "1_1") (pintype "passive"))
      (node (ref "R20") (pin "P$1") (pinfunction "P$1_P$1") (pintype "passive"))
      (node (ref "U13") (pin "7") (pinfunction "CANH_7") (pintype "bidirectional"))
    )
    (net (code "98") (name "Net-(U13-CANL)") (class "Default")
      (node (ref "JC4") (pin "2") (pinfunction "2_2") (pintype "passive"))
      (node (ref "R20") (pin "P$2") (pinfunction "P$2_P$2") (pintype "passive"))
      (node (ref "U13") (pin "6") (pinfunction "CANL_6") (pintype "bidirectional"))
    )
    (net (code "99") (name "unconnected-(J4-Pad7)") (class "Default")
      (node (ref "J4") (pin "7") (pinfunction "7_7") (pintype "passive"))
    )
    (net (code "100") (name "unconnected-(J4-Pad13)") (class "Default")
      (node (ref "J4") (pin "13") (pinfunction "13_13") (pintype "passive"))
    )
    (net (code "101") (name "unconnected-(J4-Pad22)") (class "Default")
      (node (ref "J4") (pin "22") (pinfunction "22_22") (pintype "passive"))
    )
    (net (code "102") (name "unconnected-(J4-Pad31)") (class "Default")
      (node (ref "J4") (pin "31") (pinfunction "31_31") (pintype "passive"))
    )
    (net (code "103") (name "unconnected-(JD1-Pad1)") (class "Default")
      (node (ref "JD1") (pin "1") (pinfunction "1_1") (pintype "passive"))
    )
    (net (code "104") (name "unconnected-(JD2-Pad1)") (class "Default")
      (node (ref "JD2") (pin "1") (pinfunction "1_1") (pintype "passive"))
    )
    (net (code "105") (name "unconnected-(JD3-Pad1)") (class "Default")
      (node (ref "JD3") (pin "1") (pinfunction "1_1") (pintype "passive"))
    )
    (net (code "106") (name "unconnected-(U1-CF-Pad8)") (class "Default")
      (node (ref "U1") (pin "8") (pinfunction "CF_8") (pintype "passive"))
    )
    (net (code "107") (name "unconnected-(U1-MODE-Pad11)") (class "Default")
      (node (ref "U1") (pin "11") (pinfunction "MODE_11") (pintype "passive"))
    )
    (net (code "108") (name "unconnected-(U1-RT-Pad10)") (class "Default")
      (node (ref "U1") (pin "10") (pinfunction "RT_10") (pintype "passive"))
    )
    (net (code "109") (name "unconnected-(U1-SYNC-Pad6)") (class "Default")
      (node (ref "U1") (pin "6") (pinfunction "SYNC_6") (pintype "passive"))
    )
    (net (code "110") (name "unconnected-(U1-~{RESET}-Pad5)") (class "Default")
      (node (ref "U1") (pin "5") (pinfunction "~{RESET}_5") (pintype "passive"))
    )
    (net (code "111") (name "unconnected-(U4-PA0-Pad8)") (class "Default")
      (node (ref "U4") (pin "8") (pinfunction "PA0_8") (pintype "bidirectional"))
    )
    (net (code "112") (name "unconnected-(U4-PA1-Pad9)") (class "Default")
      (node (ref "U4") (pin "9") (pinfunction "PA1_9") (pintype "bidirectional"))
    )
    (net (code "113") (name "unconnected-(U4-PA2-Pad10)") (class "Default")
      (node (ref "U4") (pin "10") (pinfunction "PA2_10") (pintype "bidirectional"))
    )
    (net (code "114") (name "unconnected-(U4-PA3-Pad11)") (class "Default")
      (node (ref "U4") (pin "11") (pinfunction "PA3_11") (pintype "bidirectional"))
    )
    (net (code "115") (name "unconnected-(U4-PA8-Pad30)") (class "Default")
      (node (ref "U4") (pin "30") (pinfunction "PA8_30") (pintype "bidirectional"))
    )
    (net (code "116") (name "unconnected-(U4-PA9-Pad31)") (class "Default")
      (node (ref "U4") (pin "31") (pinfunction "PA9_31") (pintype "bidirectional"))
    )
    (net (code "117") (name "unconnected-(U4-PA10-Pad32)") (class "Default")
      (node (ref "U4") (pin "32") (pinfunction "PA10_32") (pintype "bidirectional"))
    )
    (net (code "118") (name "unconnected-(U4-PA15-Pad38)") (class "Default")
      (node (ref "U4") (pin "38") (pinfunction "PA15_38") (pintype "bidirectional"))
    )
    (net (code "119") (name "unconnected-(U4-PB1-Pad18)") (class "Default")
      (node (ref "U4") (pin "18") (pinfunction "PB1_18") (pintype "bidirectional"))
    )
    (net (code "120") (name "unconnected-(U4-PB2-Pad19)") (class "Default")
      (node (ref "U4") (pin "19") (pinfunction "PB2_19") (pintype "bidirectional"))
    )
    (net (code "121") (name "unconnected-(U4-PB5-Pad43)") (class "Default")
      (node (ref "U4") (pin "43") (pinfunction "PB5_43") (pintype "bidirectional"))
    )
    (net (code "122") (name "unconnected-(U4-PB6-Pad44)") (class "Default")
      (node (ref "U4") (pin "44") (pinfunction "PB6_44") (pintype "bidirectional"))
    )
    (net (code "123") (name "unconnected-(U4-PB7-Pad45)") (class "Default")
      (node (ref "U4") (pin "45") (pinfunction "PB7_45") (pintype "bidirectional"))
    )
    (net (code "124") (name "unconnected-(U4-PB8-BOOT0-Pad46)") (class "Default")
      (node (ref "U4") (pin "46") (pinfunction "PB8-BOOT0_46") (pintype "bidirectional"))
    )
    (net (code "125") (name "unconnected-(U4-PB9-Pad47)") (class "Default")
      (node (ref "U4") (pin "47") (pinfunction "PB9_47") (pintype "bidirectional"))
    )
    (net (code "126") (name "unconnected-(U4-PB10-Pad22)") (class "Default")
      (node (ref "U4") (pin "22") (pinfunction "PB10_22") (pintype "bidirectional"))
    )
    (net (code "127") (name "unconnected-(U4-PB11-Pad24)") (class "Default")
      (node (ref "U4") (pin "24") (pinfunction "PB11_24") (pintype "bidirectional"))
    )
    (net (code "128") (name "unconnected-(U4-PB12-Pad25)") (class "Default")
      (node (ref "U4") (pin "25") (pinfunction "PB12_25") (pintype "bidirectional"))
    )
    (net (code "129") (name "unconnected-(U4-PB13-Pad26)") (class "Default")
      (node (ref "U4") (pin "26") (pinfunction "PB13_26") (pintype "bidirectional"))
    )
    (net (code "130") (name "unconnected-(U4-PB14-Pad27)") (class "Default")
      (node (ref "U4") (pin "27") (pinfunction "PB14_27") (pintype "bidirectional"))
    )
    (net (code "131") (name "unconnected-(U4-PB15-Pad28)") (class "Default")
      (node (ref "U4") (pin "28") (pinfunction "PB15_28") (pintype "bidirectional"))
    )
    (net (code "132") (name "unconnected-(U4-PC4-Pad16)") (class "Default")
      (node (ref "U4") (pin "16") (pinfunction "PC4_16") (pintype "bidirectional"))
    )
    (net (code "133") (name "unconnected-(U4-PC6-Pad29)") (class "Default")
      (node (ref "U4") (pin "29") (pinfunction "PC6_29") (pintype "bidirectional"))
    )
    (net (code "134") (name "unconnected-(U4-PC10-Pad39)") (class "Default")
      (node (ref "U4") (pin "39") (pinfunction "PC10_39") (pintype "bidirectional"))
    )
    (net (code "135") (name "unconnected-(U4-PC11-Pad40)") (class "Default")
      (node (ref "U4") (pin "40") (pinfunction "PC11_40") (pintype "bidirectional"))
    )
    (net (code "136") (name "unconnected-(U4-PC13-Pad2)") (class "Default")
      (node (ref "U4") (pin "2") (pinfunction "PC13_2") (pintype "bidirectional"))
    )
    (net (code "137") (name "unconnected-(U7-PA0-Pad8)") (class "Default")
      (node (ref "U7") (pin "8") (pinfunction "PA0_8") (pintype "bidirectional"))
    )
    (net (code "138") (name "unconnected-(U7-PA1-Pad9)") (class "Default")
      (node (ref "U7") (pin "9") (pinfunction "PA1_9") (pintype "bidirectional"))
    )
    (net (code "139") (name "unconnected-(U7-PA2-Pad10)") (class "Default")
      (node (ref "U7") (pin "10") (pinfunction "PA2_10") (pintype "bidirectional"))
    )
    (net (code "140") (name "unconnected-(U7-PA3-Pad11)") (class "Default")
      (node (ref "U7") (pin "11") (pinfunction "PA3_11") (pintype "bidirectional"))
    )
    (net (code "141") (name "unconnected-(U7-PA15-Pad38)") (class "Default")
      (node (ref "U7") (pin "38") (pinfunction "PA15_38") (pintype "bidirectional"))
    )
    (net (code "142") (name "unconnected-(U7-PB3-Pad41)") (class "Default")
      (node (ref "U7") (pin "41") (pinfunction "PB3_41") (pintype "bidirectional"))
    )
    (net (code "143") (name "unconnected-(U7-PB4-Pad42)") (class "Default")
      (node (ref "U7") (pin "42") (pinfunction "PB4_42") (pintype "bidirectional"))
    )
    (net (code "144") (name "unconnected-(U7-PB5-Pad43)") (class "Default")
      (node (ref "U7") (pin "43") (pinfunction "PB5_43") (pintype "bidirectional"))
    )
    (net (code "145") (name "unconnected-(U7-PB6-Pad44)") (class "Default")
      (node (ref "U7") (pin "44") (pinfunction "PB6_44") (pintype "bidirectional"))
    )
    (net (code "146") (name "unconnected-(U7-PB7-Pad45)") (class "Default")
      (node (ref "U7") (pin "45") (pinfunction "PB7_45") (pintype "bidirectional"))
    )
    (net (code "147") (name "unconnected-(U7-PB8-BOOT0-Pad46)") (class "Default")
      (node (ref "U7") (pin "46") (pinfunction "PB8-BOOT0_46") (pintype "bidirectional"))
    )
    (net (code "148") (name "unconnected-(U7-PB9-Pad47)") (class "Default")
      (node (ref "U7") (pin "47") (pinfunction "PB9_47") (pintype "bidirectional"))
    )
    (net (code "149") (name "unconnected-(U7-PC6-Pad29)") (class "Default")
      (node (ref "U7") (pin "29") (pinfunction "PC6_29") (pintype "bidirectional"))
    )
    (net (code "150") (name "unconnected-(U7-PC10-Pad39)") (class "Default")
      (node (ref "U7") (pin "39") (pinfunction "PC10_39") (pintype "bidirectional"))
    )
    (net (code "151") (name "unconnected-(U7-PC11-Pad40)") (class "Default")
      (node (ref "U7") (pin "40") (pinfunction "PC11_40") (pintype "bidirectional"))
    )
    (net (code "152") (name "unconnected-(U7-PC13-Pad2)") (class "Default")
      (node (ref "U7") (pin "2") (pinfunction "PC13_2") (pintype "bidirectional"))
    )
    (net (code "153") (name "unconnected-(U8-INT2-Pad1)") (class "Default")
      (node (ref "U8") (pin "1") (pinfunction "INT2_1") (pintype "bidirectional"))
    )
    (net (code "154") (name "unconnected-(U8-INT4-Pad13)") (class "Default")
      (node (ref "U8") (pin "13") (pinfunction "INT4_13") (pintype "bidirectional"))
    )
    (net (code "155") (name "unconnected-(U8-NC-Pad2)") (class "Default")
      (node (ref "U8") (pin "2") (pinfunction "NC_2") (pintype "bidirectional"))
    )
    (net (code "156") (name "unconnected-(U11-PA0-Pad8)") (class "Default")
      (node (ref "U11") (pin "8") (pinfunction "PA0_8") (pintype "bidirectional"))
    )
    (net (code "157") (name "unconnected-(U11-PA1-Pad9)") (class "Default")
      (node (ref "U11") (pin "9") (pinfunction "PA1_9") (pintype "bidirectional"))
    )
    (net (code "158") (name "unconnected-(U11-PA2-Pad10)") (class "Default")
      (node (ref "U11") (pin "10") (pinfunction "PA2_10") (pintype "bidirectional"))
    )
    (net (code "159") (name "unconnected-(U11-PA3-Pad11)") (class "Default")
      (node (ref "U11") (pin "11") (pinfunction "PA3_11") (pintype "bidirectional"))
    )
    (net (code "160") (name "unconnected-(U11-PA8-Pad30)") (class "Default")
      (node (ref "U11") (pin "30") (pinfunction "PA8_30") (pintype "bidirectional"))
    )
    (net (code "161") (name "unconnected-(U11-PA9-Pad31)") (class "Default")
      (node (ref "U11") (pin "31") (pinfunction "PA9_31") (pintype "bidirectional"))
    )
    (net (code "162") (name "unconnected-(U11-PA10-Pad32)") (class "Default")
      (node (ref "U11") (pin "32") (pinfunction "PA10_32") (pintype "bidirectional"))
    )
    (net (code "163") (name "unconnected-(U11-PA15-Pad38)") (class "Default")
      (node (ref "U11") (pin "38") (pinfunction "PA15_38") (pintype "bidirectional"))
    )
    (net (code "164") (name "unconnected-(U11-PB1-Pad18)") (class "Default")
      (node (ref "U11") (pin "18") (pinfunction "PB1_18") (pintype "bidirectional"))
    )
    (net (code "165") (name "unconnected-(U11-PB2-Pad19)") (class "Default")
      (node (ref "U11") (pin "19") (pinfunction "PB2_19") (pintype "bidirectional"))
    )
    (net (code "166") (name "unconnected-(U11-PB5-Pad43)") (class "Default")
      (node (ref "U11") (pin "43") (pinfunction "PB5_43") (pintype "bidirectional"))
    )
    (net (code "167") (name "unconnected-(U11-PB6-Pad44)") (class "Default")
      (node (ref "U11") (pin "44") (pinfunction "PB6_44") (pintype "bidirectional"))
    )
    (net (code "168") (name "unconnected-(U11-PB7-Pad45)") (class "Default")
      (node (ref "U11") (pin "45") (pinfunction "PB7_45") (pintype "bidirectional"))
    )
    (net (code "169") (name "unconnected-(U11-PB8-BOOT0-Pad46)") (class "Default")
      (node (ref "U11") (pin "46") (pinfunction "PB8-BOOT0_46") (pintype "bidirectional"))
    )
    (net (code "170") (name "unconnected-(U11-PB9-Pad47)") (class "Default")
      (node (ref "U11") (pin "47") (pinfunction "PB9_47") (pintype "bidirectional"))
    )
    (net (code "171") (name "unconnected-(U11-PB10-Pad22)") (class "Default")
      (node (ref "U11") (pin "22") (pinfunction "PB10_22") (pintype "bidirectional"))
    )
    (net (code "172") (name "unconnected-(U11-PB11-Pad24)") (class "Default")
      (node (ref "U11") (pin "24") (pinfunction "PB11_24") (pintype "bidirectional"))
    )
    (net (code "173") (name "unconnected-(U11-PB12-Pad25)") (class "Default")
      (node (ref "U11") (pin "25") (pinfunction "PB12_25") (pintype "bidirectional"))
    )
    (net (code "174") (name "unconnected-(U11-PB13-Pad26)") (class "Default")
      (node (ref "U11") (pin "26") (pinfunction "PB13_26") (pintype "bidirectional"))
    )
    (net (code "175") (name "unconnected-(U11-PB14-Pad27)") (class "Default")
      (node (ref "U11") (pin "27") (pinfunction "PB14_27") (pintype "bidirectional"))
    )
    (net (code "176") (name "unconnected-(U11-PB15-Pad28)") (class "Default")
      (node (ref "U11") (pin "28") (pinfunction "PB15_28") (pintype "bidirectional"))
    )
    (net (code "177") (name "unconnected-(U11-PC4-Pad16)") (class "Default")
      (node (ref "U11") (pin "16") (pinfunction "PC4_16") (pintype "bidirectional"))
    )
    (net (code "178") (name "unconnected-(U11-PC6-Pad29)") (class "Default")
      (node (ref "U11") (pin "29") (pinfunction "PC6_29") (pintype "bidirectional"))
    )
    (net (code "179") (name "unconnected-(U11-PC10-Pad39)") (class "Default")
      (node (ref "U11") (pin "39") (pinfunction "PC10_39") (pintype "bidirectional"))
    )
    (net (code "180") (name "unconnected-(U11-PC11-Pad40)") (class "Default")
      (node (ref "U11") (pin "40") (pinfunction "PC11_40") (pintype "bidirectional"))
    )
    (net (code "181") (name "unconnected-(U11-PC13-Pad2)") (class "Default")
      (node (ref "U11") (pin "2") (pinfunction "PC13_2") (pintype "bidirectional"))
    )
    (net (code "182") (name "unconnected-(U14-RESV_2-Pad2)") (class "Default")
      (node (ref "U14") (pin "2") (pinfunction "RESV_2_2") (pintype "passive"))
    )
    (net (code "183") (name "unconnected-(U14-RESV_3-Pad3)") (class "Default")
      (node (ref "U14") (pin "3") (pinfunction "RESV_3_3") (pintype "passive"))
    )
    (net (code "184") (name "unconnected-(U14-RESV_7-Pad7)") (class "Default")
      (node (ref "U14") (pin "7") (pinfunction "RESV_7_7") (pintype "passive"))
    )
    (net (code "185") (name "unconnected-(U14-RESV_10-Pad10)") (class "Default")
      (node (ref "U14") (pin "10") (pinfunction "RESV_10_10") (pintype "passive"))
    )
    (net (code "186") (name "unconnected-(U14-RESV_11-Pad11)") (class "Default")
      (node (ref "U14") (pin "11") (pinfunction "RESV_11_11") (pintype "passive"))
    )
  )
)
